# io-board-c-7.net
KiCad netlist of a schematic drawn in EAGLE
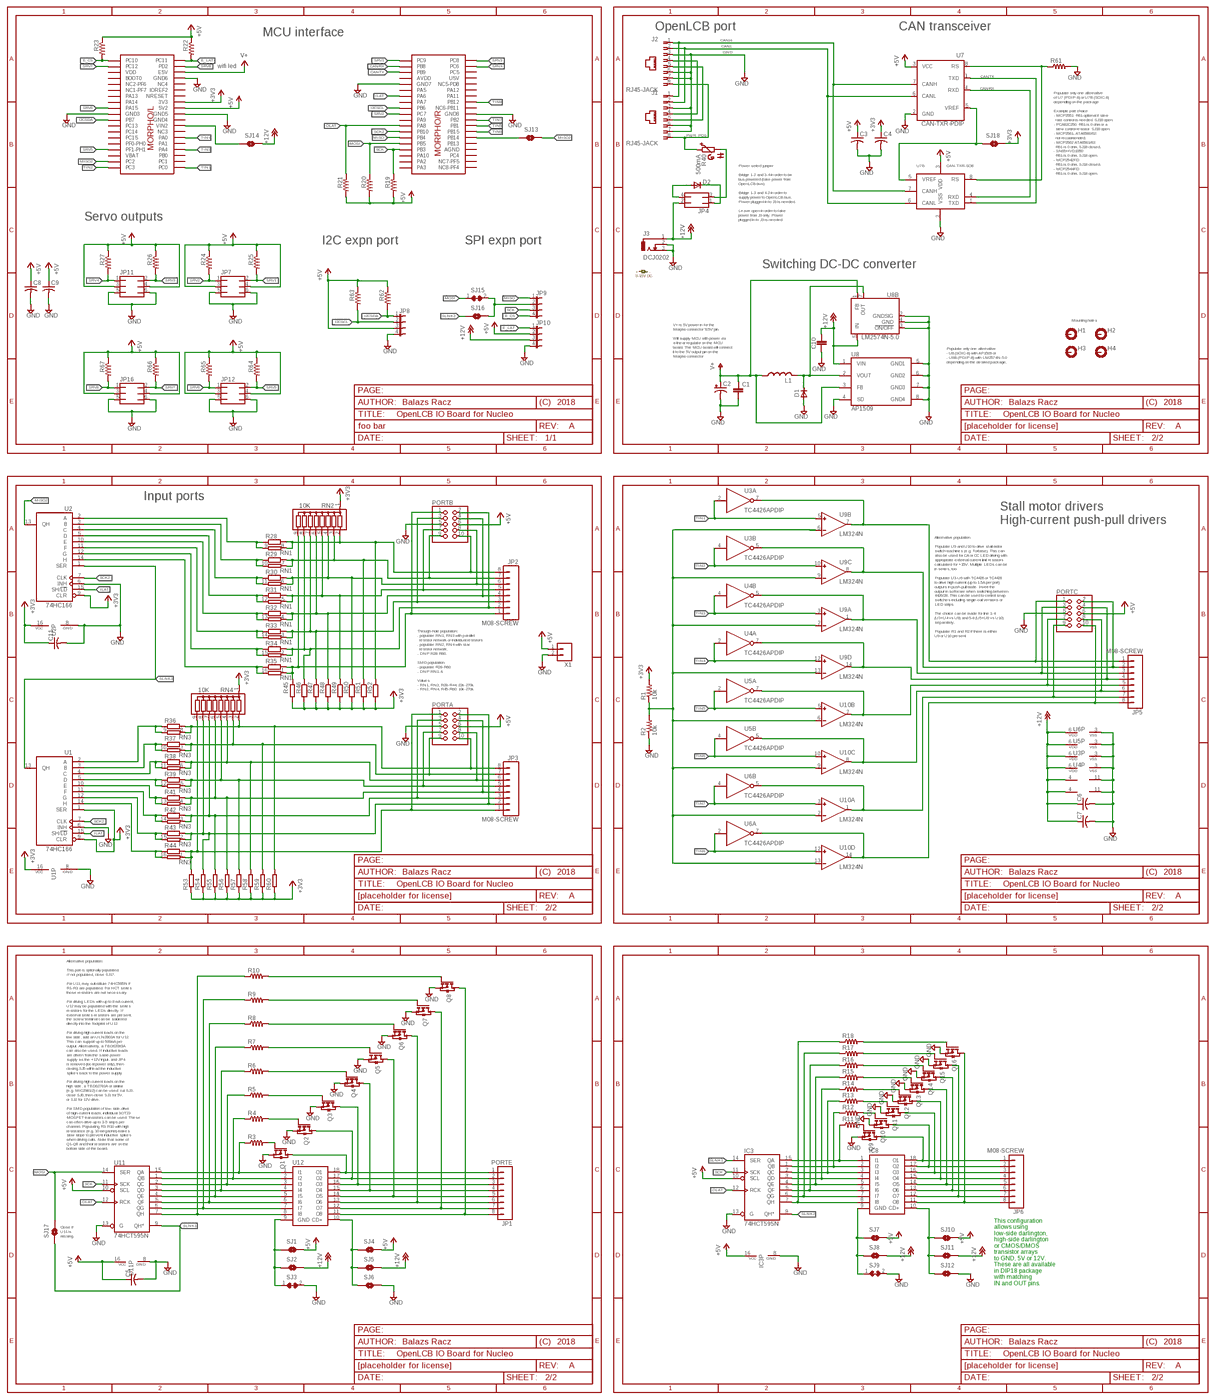
[diagram p0: schematic, sheet 1, overview]
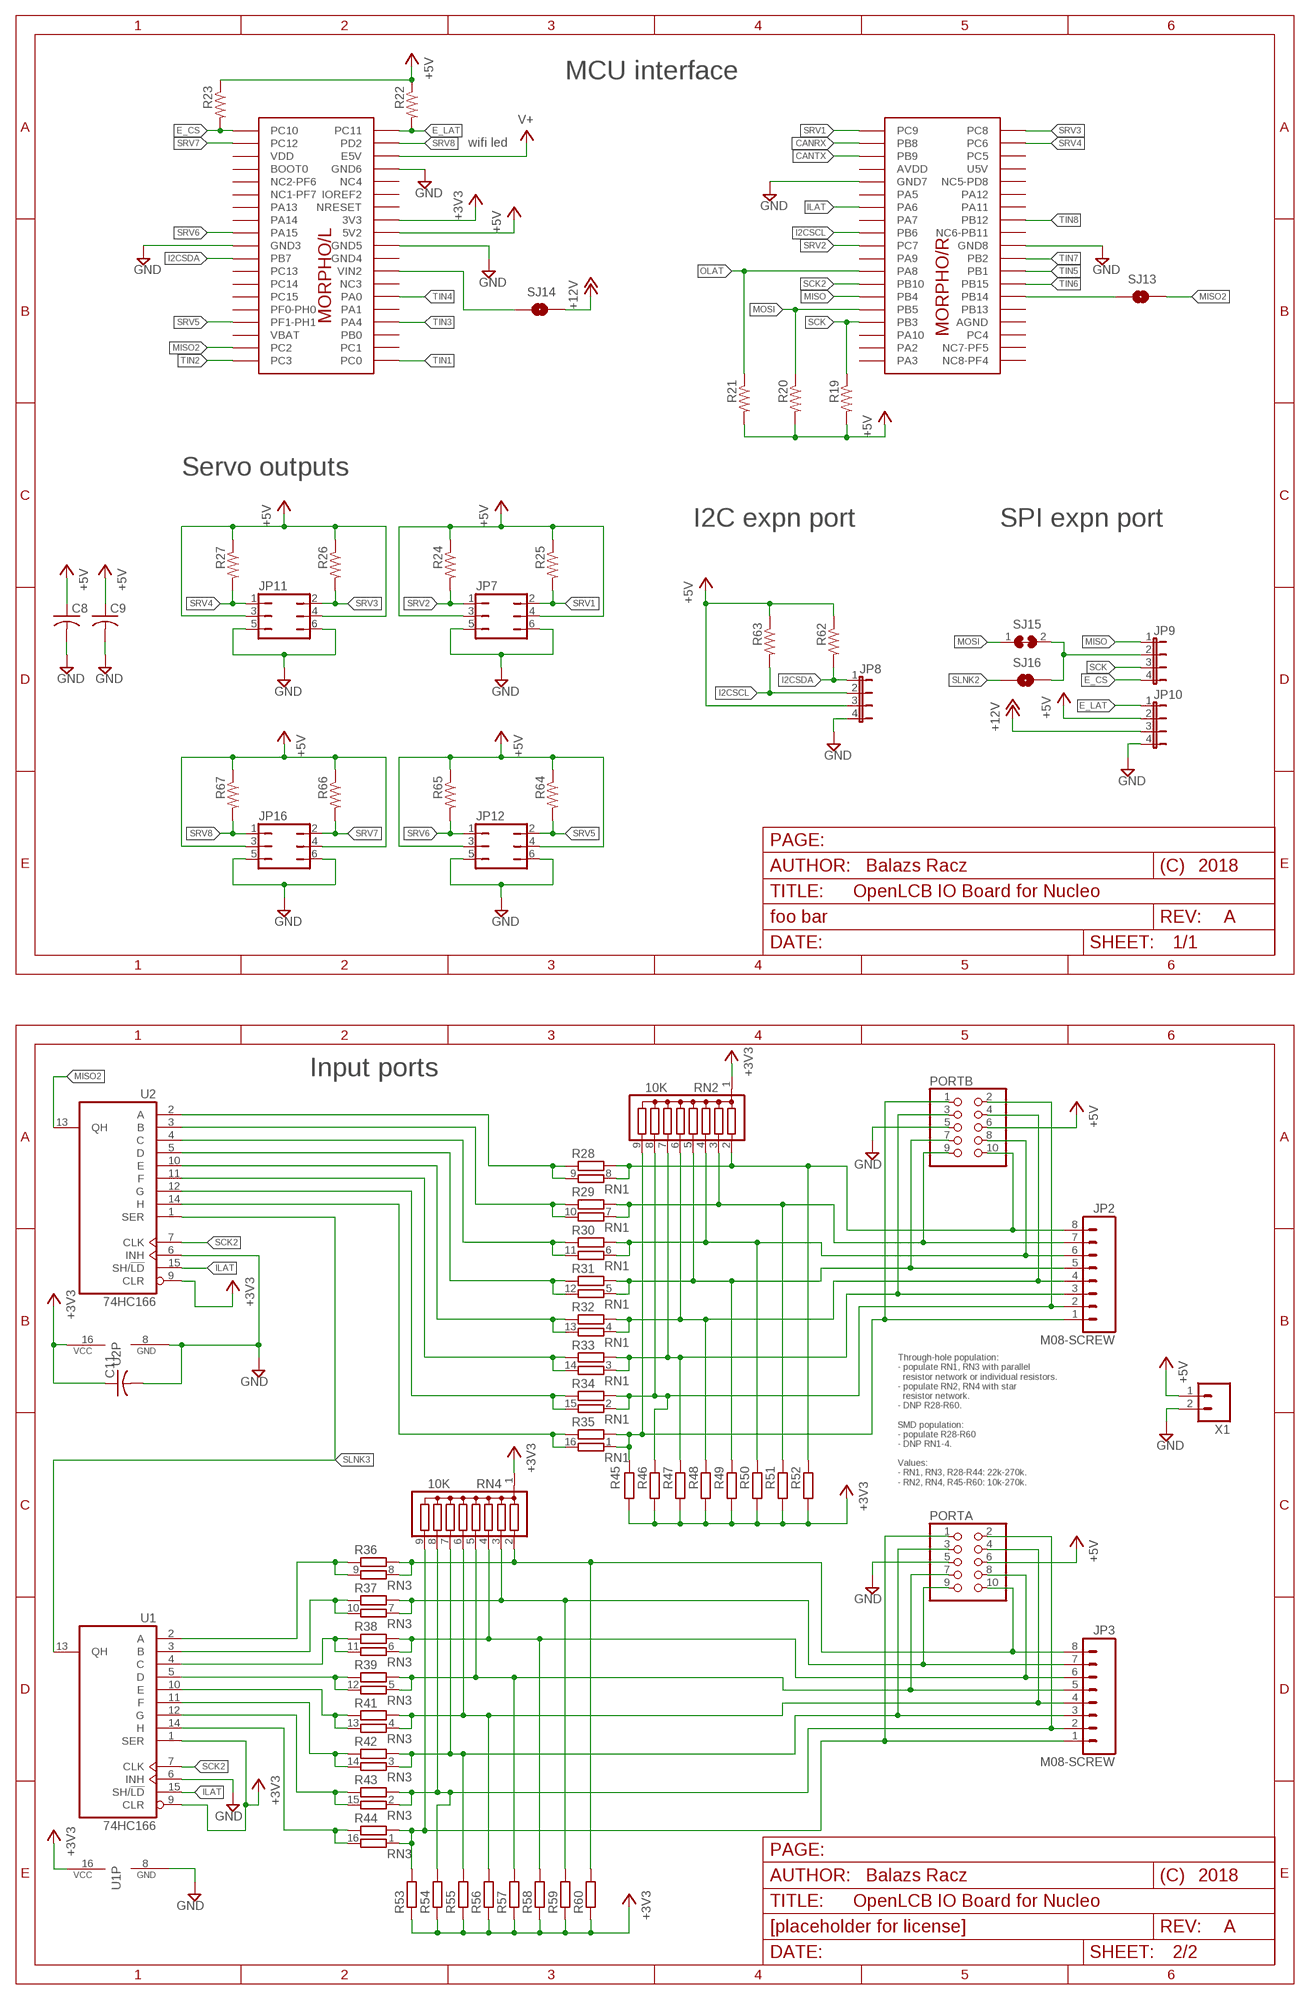
[diagram p1: schematic, sheet 1, part 1 of 4]
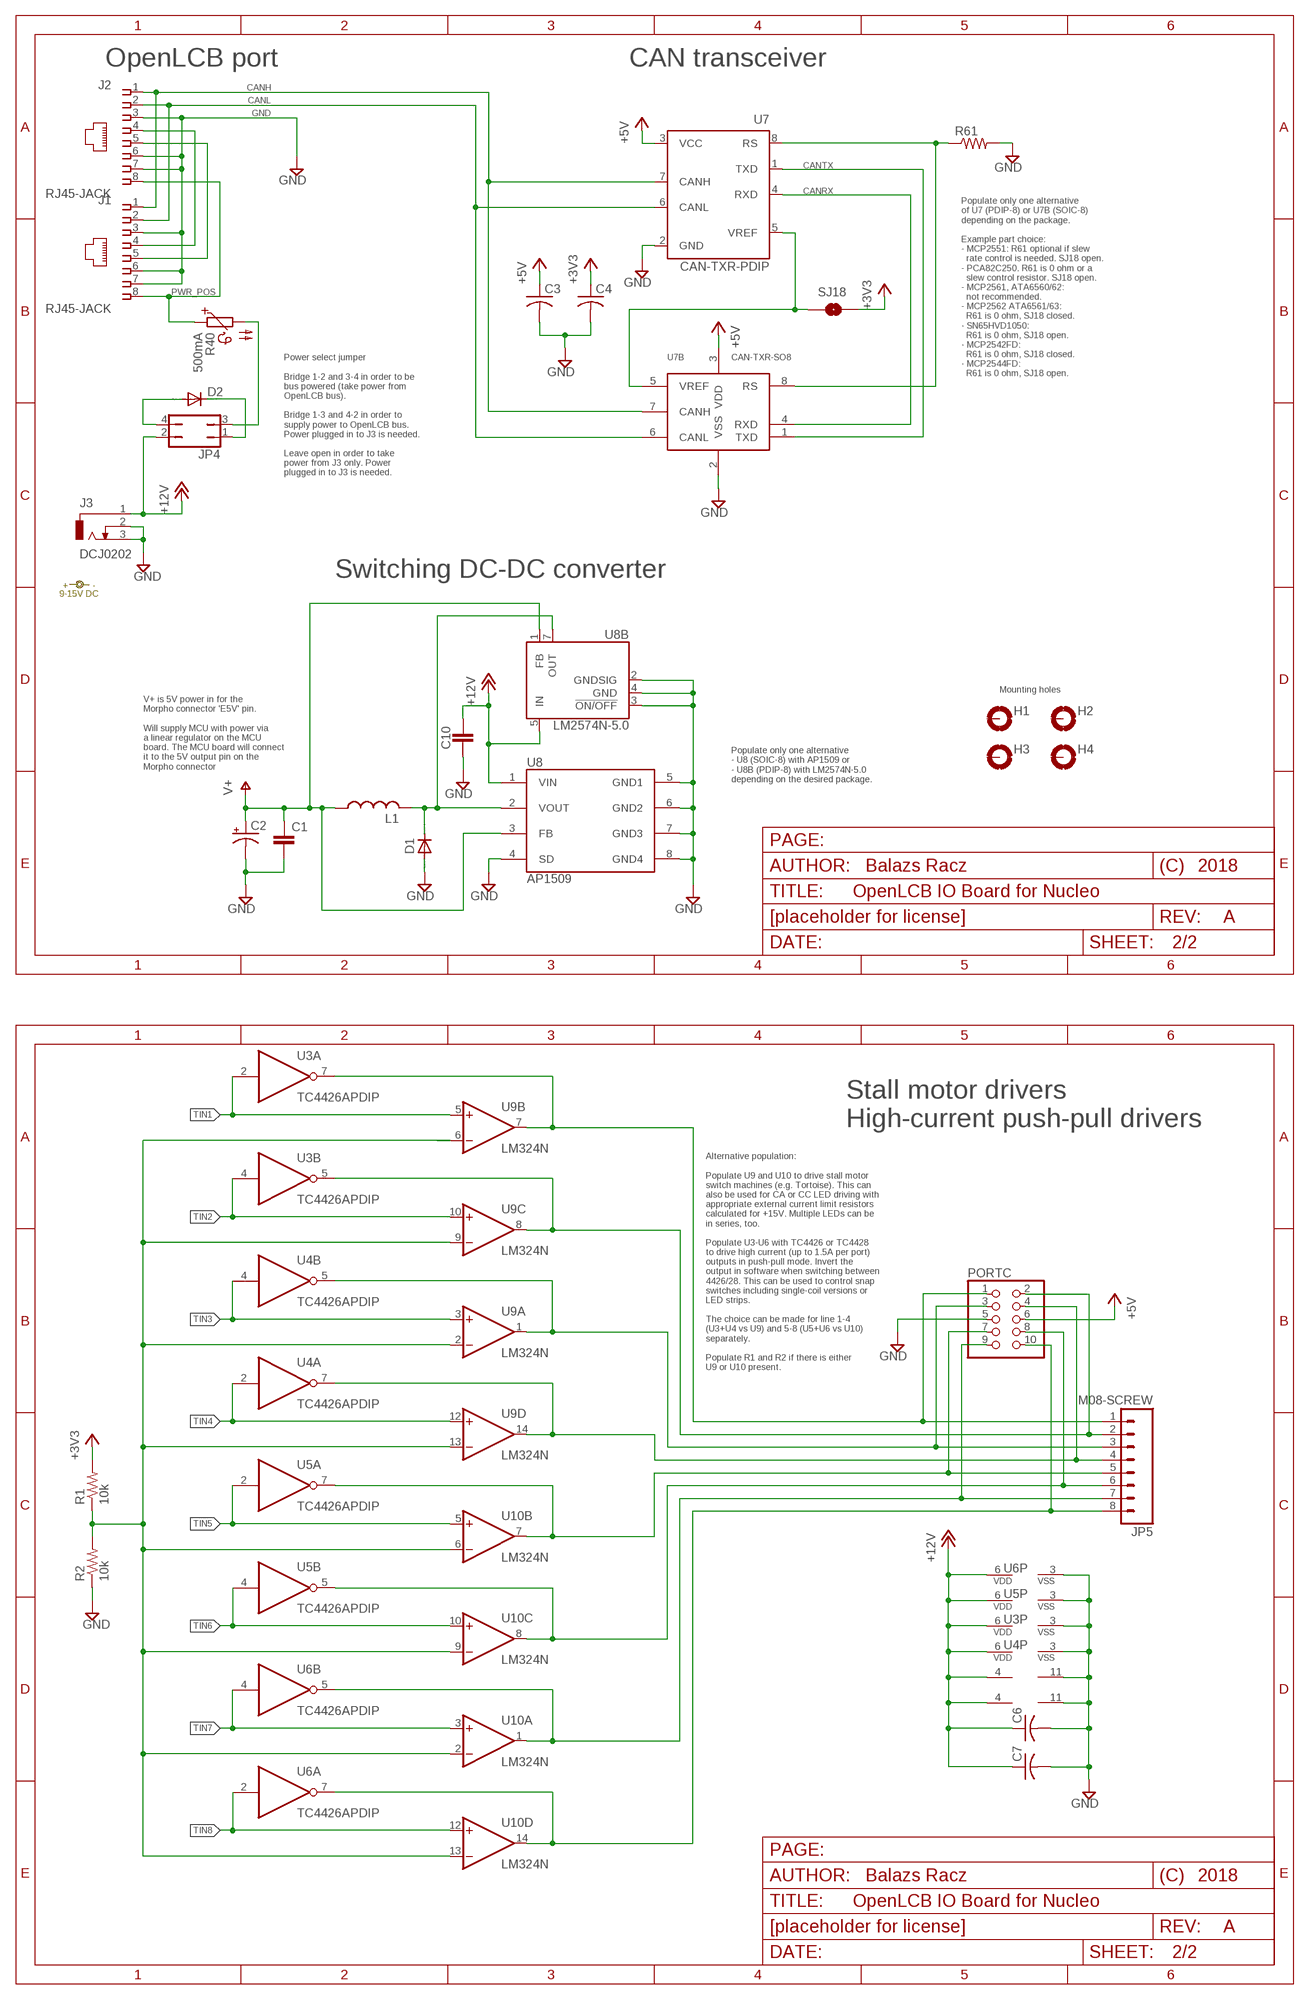
[diagram p2: schematic, sheet 1, part 2 of 4]
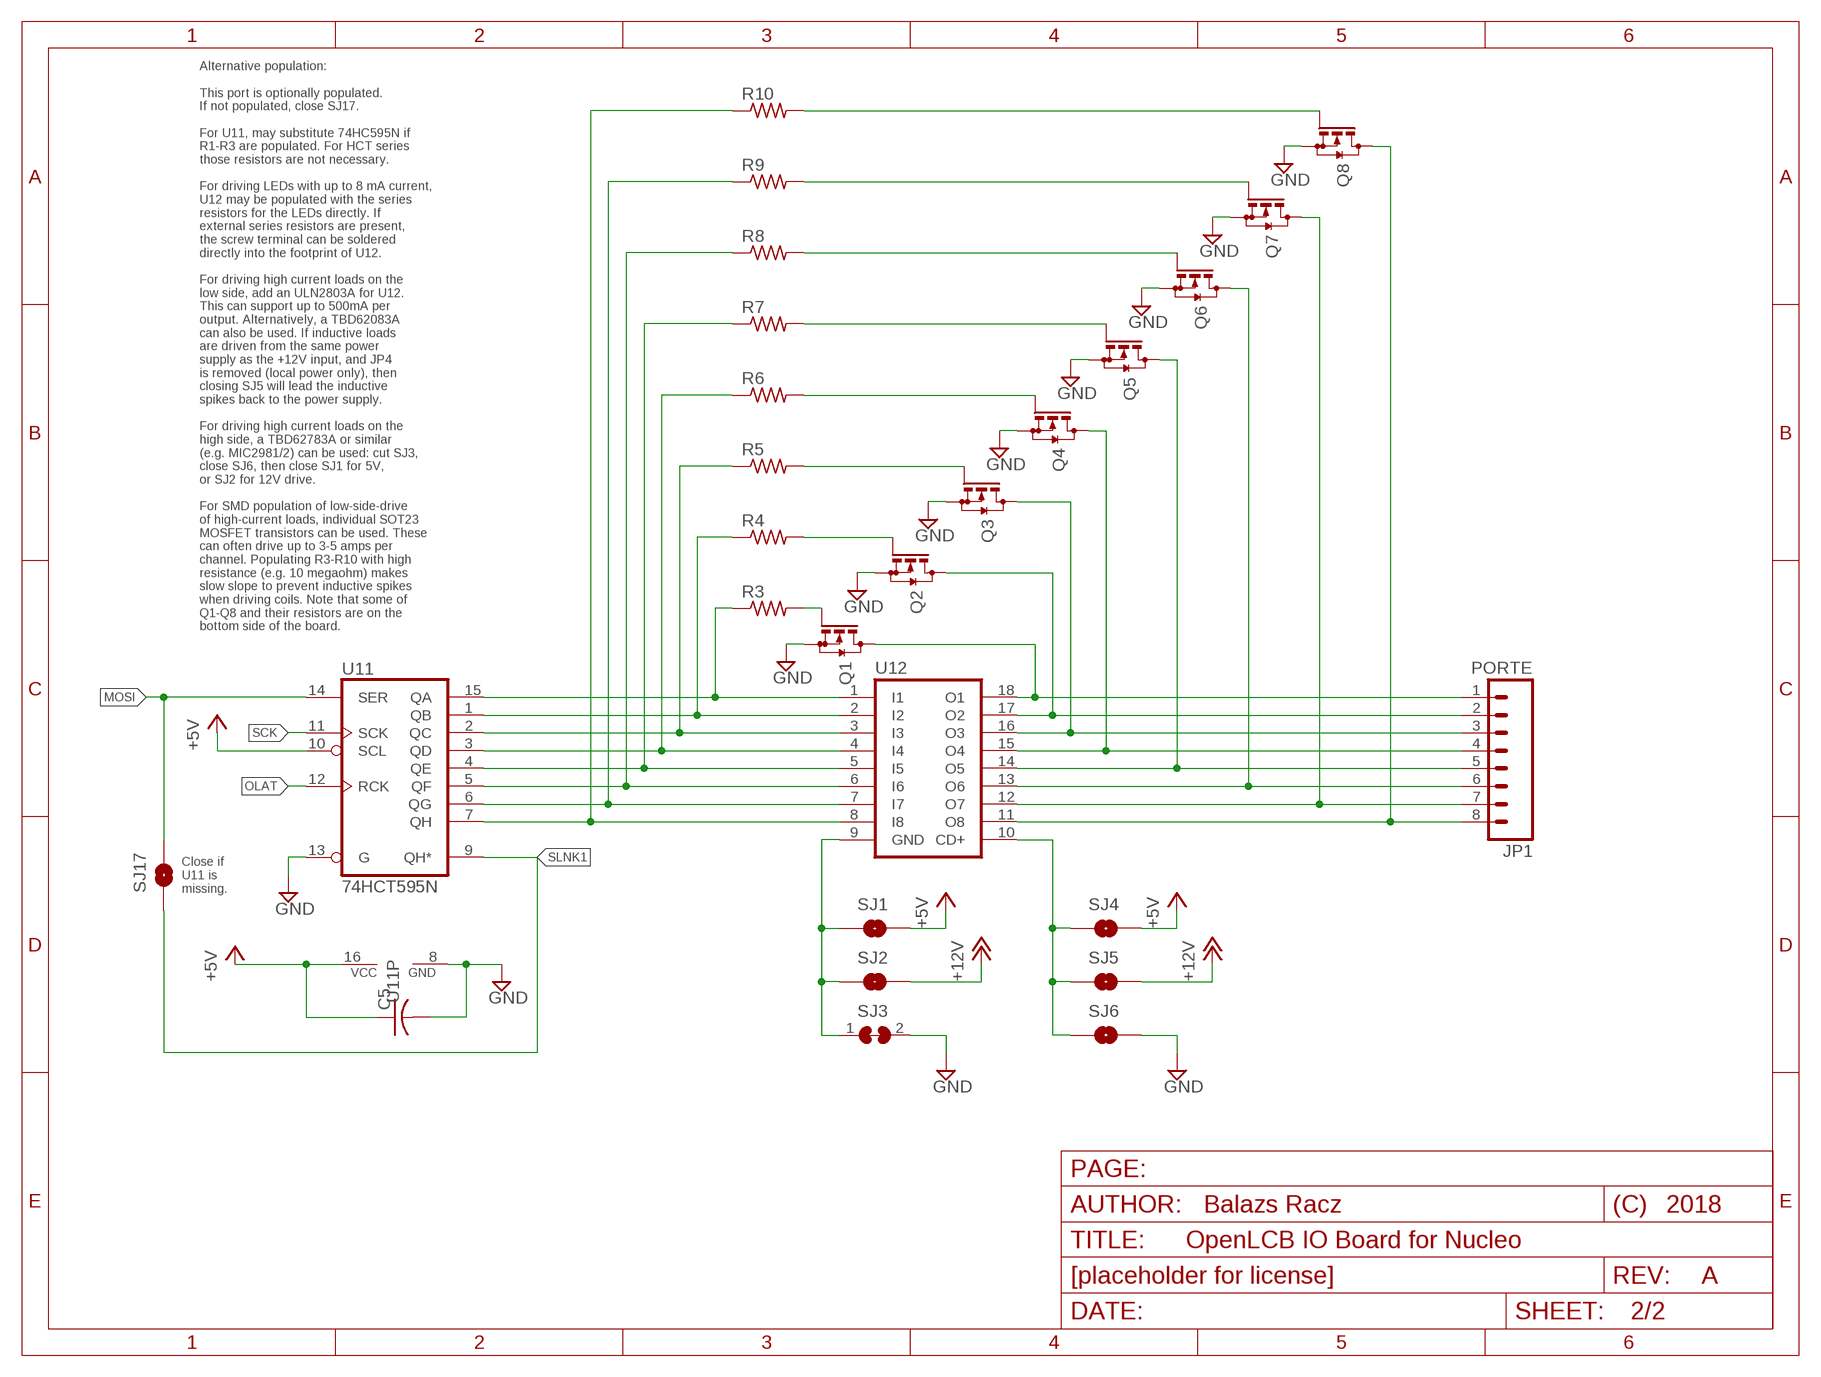
[diagram p3: schematic, sheet 1, part 3 of 4]
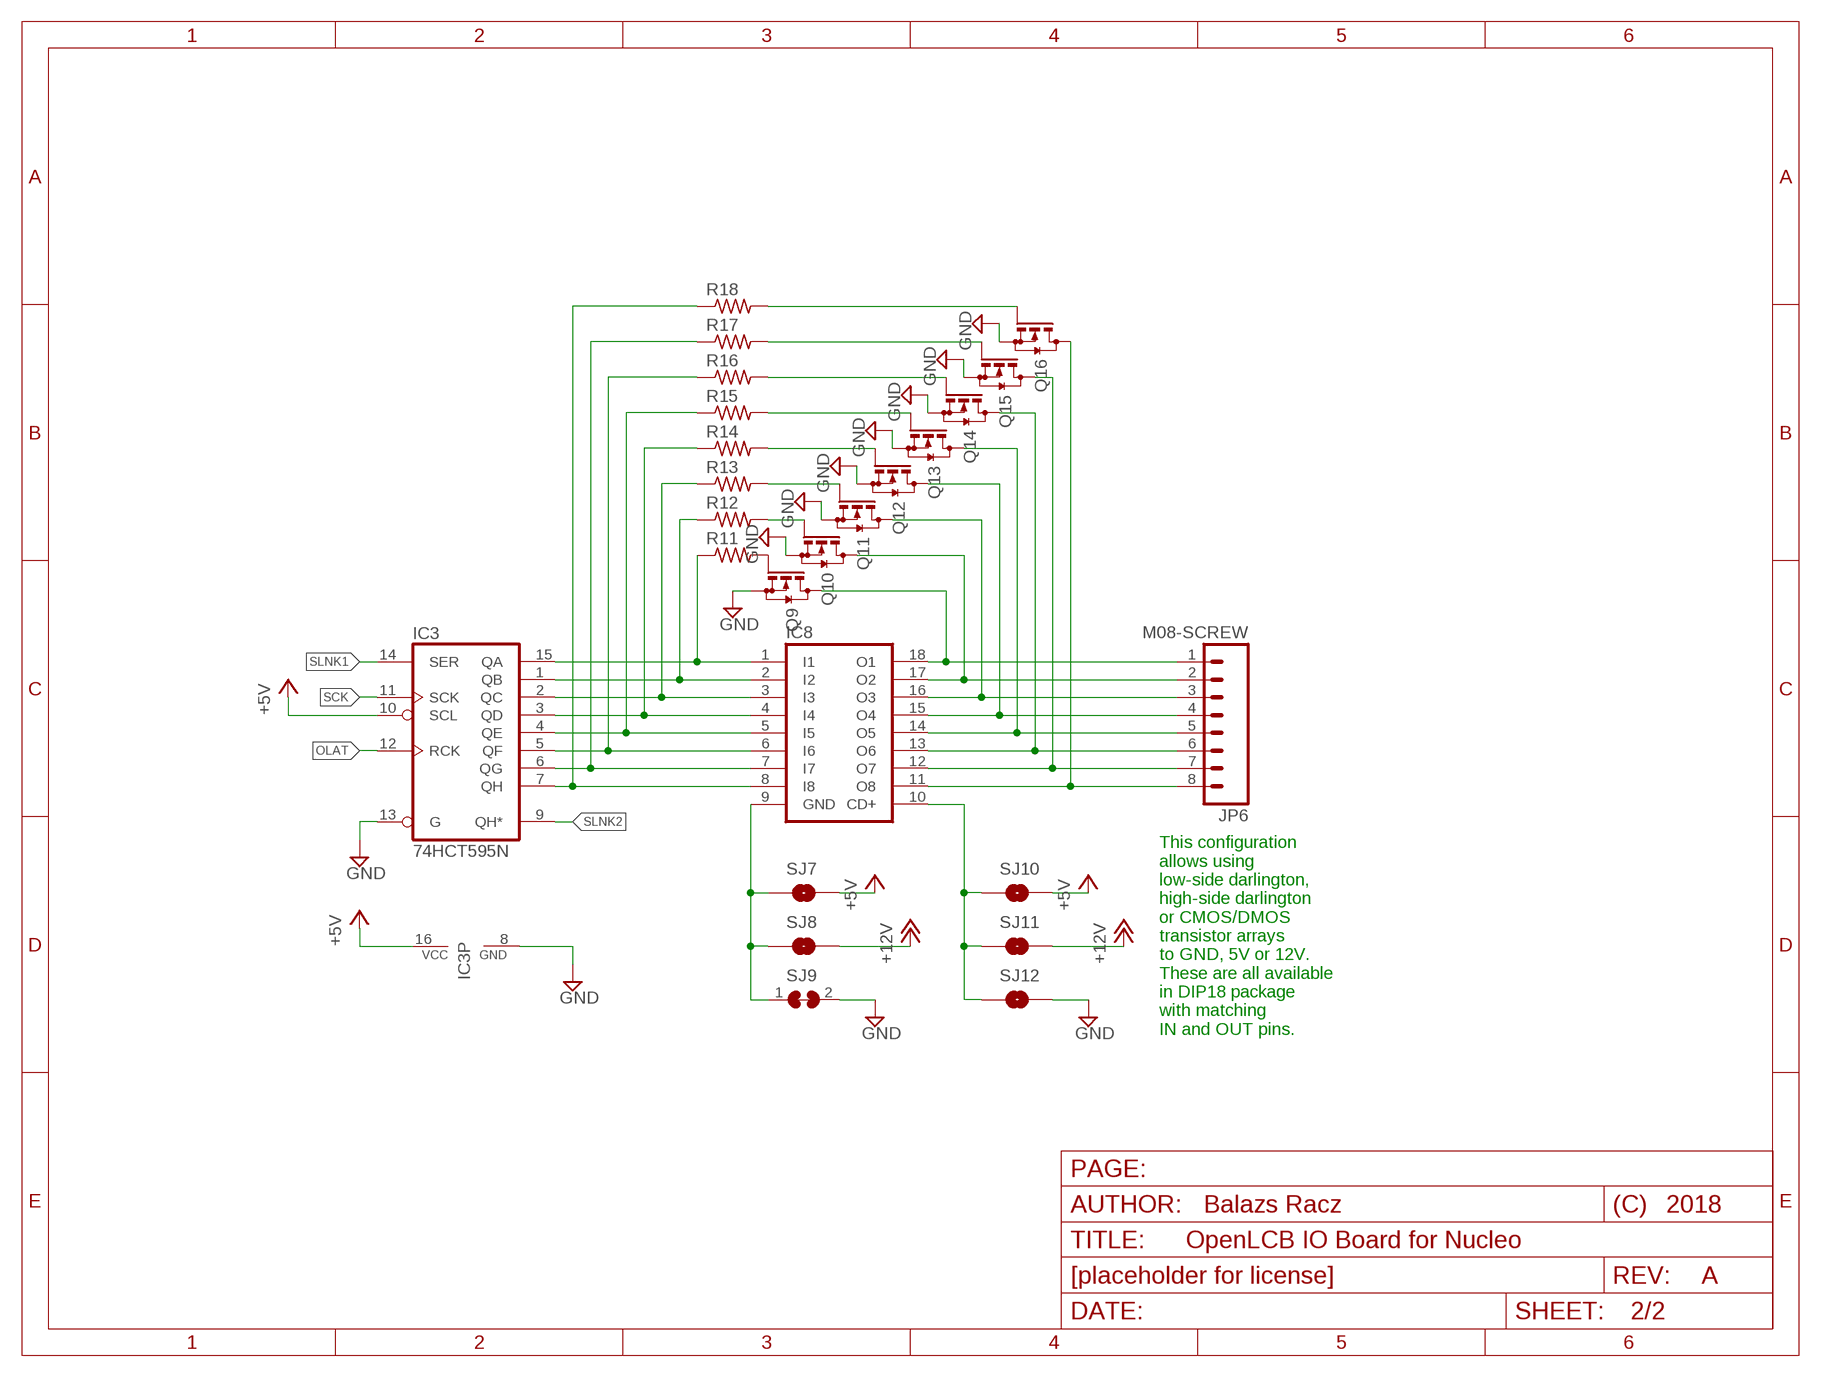
[diagram p4: schematic, sheet 1, part 4 of 4]

(export (version "E")
  (design (tool "Eeschema 10.0.6"))
  (components
    (comp (ref "+12V")
      (value "9-15V DC")
      (footprint "eagle-import:POWER_USAGE")
      (libsource (lib "eagle-import") (part "DOC-POWER_LABEL"))
    )
    (comp (ref "C1")
      (value "C-EUC1206")
      (footprint "eagle-import:C1206")
      (libsource (lib "eagle-import") (part "C-EUC1206"))
    )
    (comp (ref "C2")
      (value "CPOL-USE2.5-5")
      (footprint "eagle-import:E2,5-5")
      (libsource (lib "eagle-import") (part "CPOL-USE2.5-5"))
    )
    (comp (ref "C3")
      (value "C-USC0805")
      (footprint "eagle-import:C0805")
      (libsource (lib "eagle-import") (part "C-USC0805"))
    )
    (comp (ref "C4")
      (value "C-USC0805")
      (footprint "eagle-import:C0805")
      (libsource (lib "eagle-import") (part "C-USC0805"))
    )
    (comp (ref "C5")
      (value "C-USC0805")
      (footprint "eagle-import:C0805")
      (libsource (lib "eagle-import") (part "C-USC0805"))
    )
    (comp (ref "C6")
      (value "C-USC1206")
      (footprint "eagle-import:C1206")
      (libsource (lib "eagle-import") (part "C-USC1206"))
    )
    (comp (ref "C7")
      (value "C-USC1206")
      (footprint "eagle-import:C1206")
      (libsource (lib "eagle-import") (part "C-USC1206"))
    )
    (comp (ref "C8")
      (value "C-USC1206")
      (footprint "eagle-import:C1206")
      (libsource (lib "eagle-import") (part "C-USC1206"))
    )
    (comp (ref "C9")
      (value "C-USC1206")
      (footprint "eagle-import:C1206")
      (libsource (lib "eagle-import") (part "C-USC1206"))
    )
    (comp (ref "C10")
      (value "C-EUC1206")
      (footprint "eagle-import:C1206")
      (libsource (lib "eagle-import") (part "C-EUC1206"))
    )
    (comp (ref "C11")
      (value "C-USC0805")
      (footprint "eagle-import:C0805")
      (libsource (lib "eagle-import") (part "C-USC0805"))
    )
    (comp (ref "D1")
      (value "DIODE-DO41-7.6")
      (footprint "eagle-import:DO41-7.6")
      (libsource (lib "eagle-import") (part "DIODE-DO41-7.6"))
    )
    (comp (ref "D2")
      (value "DIODE-DO41-7.6")
      (footprint "eagle-import:DO41-7.6")
      (libsource (lib "eagle-import") (part "DIODE-DO41-7.6"))
    )
    (comp (ref "H1")
      (value "MOUNT-PAD-ROUND3.3")
      (footprint "eagle-import:3,3-PAD")
      (libsource (lib "eagle-import") (part "MOUNT-PAD-ROUND3.3"))
    )
    (comp (ref "H2")
      (value "MOUNT-PAD-ROUND3.3")
      (footprint "eagle-import:3,3-PAD")
      (libsource (lib "eagle-import") (part "MOUNT-PAD-ROUND3.3"))
    )
    (comp (ref "H3")
      (value "MOUNT-PAD-ROUND3.3")
      (footprint "eagle-import:3,3-PAD")
      (libsource (lib "eagle-import") (part "MOUNT-PAD-ROUND3.3"))
    )
    (comp (ref "H4")
      (value "MOUNT-PAD-ROUND3.3")
      (footprint "eagle-import:3,3-PAD")
      (libsource (lib "eagle-import") (part "MOUNT-PAD-ROUND3.3"))
    )
    (comp (ref "IC3")
      (value "74HCT595N")
      (footprint "eagle-import:DIL16")
      (libsource (lib "eagle-import") (part "74595NHCT"))
    )
    (comp (ref "IC8")
      (value "ULN2803A")
      (footprint "eagle-import:DIL18-THIN")
      (libsource (lib "eagle-import") (part "ULN2803A"))
    )
    (comp (ref "J1")
      (value "RJ45-JACK")
      (footprint "eagle-import:RJ45-PULSE-E5J88")
      (libsource (lib "eagle-import") (part "RJ45-JACKRJ45-PULSE-E5J00"))
    )
    (comp (ref "J2")
      (value "RJ45-JACK")
      (footprint "eagle-import:RJ45-PULSE-E5J88")
      (libsource (lib "eagle-import") (part "RJ45-JACKRJ45-PULSE-E5J00"))
    )
    (comp (ref "J3")
      (value "DCJ0202")
      (footprint "eagle-import:DCJ0202")
      (libsource (lib "eagle-import") (part "DCJ0202"))
    )
    (comp (ref "JP1")
      (value "PORTE")
      (footprint "eagle-import:1X08_TERMINAL")
      (libsource (lib "eagle-import") (part "M08-SCREW"))
    )
    (comp (ref "JP2")
      (value "M08-SCREW")
      (footprint "eagle-import:1X08_TERMINAL")
      (libsource (lib "eagle-import") (part "M08-SCREW"))
    )
    (comp (ref "JP3")
      (value "M08-SCREW")
      (footprint "eagle-import:1X08_TERMINAL")
      (libsource (lib "eagle-import") (part "M08-SCREW"))
    )
    (comp (ref "JP4")
      (value "JP2Q")
      (footprint "eagle-import:JP2Q")
      (libsource (lib "eagle-import") (part "JP2Q"))
    )
    (comp (ref "JP5")
      (value "M08-SCREW")
      (footprint "eagle-import:1X08_TERMINAL")
      (libsource (lib "eagle-import") (part "M08-SCREW"))
    )
    (comp (ref "JP6")
      (value "M08-SCREW")
      (footprint "eagle-import:1X08_TERMINAL")
      (libsource (lib "eagle-import") (part "M08-SCREW"))
    )
    (comp (ref "JP7")
      (value "JP3Q")
      (footprint "eagle-import:JP3Q")
      (libsource (lib "eagle-import") (part "JP3Q"))
    )
    (comp (ref "JP8")
      (value "JP4-FLAT")
      (footprint "eagle-import:JP4F")
      (libsource (lib "eagle-import") (part "JP4-FLAT"))
    )
    (comp (ref "JP9")
      (value "JP4-FLAT")
      (footprint "eagle-import:JP4F")
      (libsource (lib "eagle-import") (part "JP4-FLAT"))
    )
    (comp (ref "JP10")
      (value "JP4-FLAT")
      (footprint "eagle-import:JP4F")
      (libsource (lib "eagle-import") (part "JP4-FLAT"))
    )
    (comp (ref "JP11")
      (value "JP3Q")
      (footprint "eagle-import:JP3Q")
      (libsource (lib "eagle-import") (part "JP3Q"))
    )
    (comp (ref "JP12")
      (value "JP3Q")
      (footprint "eagle-import:JP3Q")
      (libsource (lib "eagle-import") (part "JP3Q"))
    )
    (comp (ref "JP16")
      (value "JP3Q")
      (footprint "eagle-import:JP3Q")
      (libsource (lib "eagle-import") (part "JP3Q"))
    )
    (comp (ref "L1")
      (value "L-US")
      (footprint "eagle-import:L5-8,5")
      (libsource (lib "eagle-import") (part "L-US"))
    )
    (comp (ref "PORTA")
      (value "PINHD-2X5CN")
      (footprint "eagle-import:CON10M")
      (libsource (lib "eagle-import") (part "PINHD-2X5CN"))
    )
    (comp (ref "PORTB")
      (value "PINHD-2X5CN")
      (footprint "eagle-import:CON10M")
      (libsource (lib "eagle-import") (part "PINHD-2X5CN"))
    )
    (comp (ref "PORTC")
      (value "PINHD-2X5CN")
      (footprint "eagle-import:CON10M")
      (libsource (lib "eagle-import") (part "PINHD-2X5CN"))
    )
    (comp (ref "Q1")
      (value "BSS123")
      (footprint "eagle-import:SOT23")
      (libsource (lib "eagle-import") (part "BSS123"))
    )
    (comp (ref "Q2")
      (value "BSS123")
      (footprint "eagle-import:SOT23")
      (libsource (lib "eagle-import") (part "BSS123"))
    )
    (comp (ref "Q3")
      (value "BSS123")
      (footprint "eagle-import:SOT23")
      (libsource (lib "eagle-import") (part "BSS123"))
    )
    (comp (ref "Q4")
      (value "BSS123")
      (footprint "eagle-import:SOT23")
      (libsource (lib "eagle-import") (part "BSS123"))
    )
    (comp (ref "Q5")
      (value "BSS123")
      (footprint "eagle-import:SOT23")
      (libsource (lib "eagle-import") (part "BSS123"))
    )
    (comp (ref "Q6")
      (value "BSS123")
      (footprint "eagle-import:SOT23")
      (libsource (lib "eagle-import") (part "BSS123"))
    )
    (comp (ref "Q7")
      (value "BSS123")
      (footprint "eagle-import:SOT23")
      (libsource (lib "eagle-import") (part "BSS123"))
    )
    (comp (ref "Q8")
      (value "BSS123")
      (footprint "eagle-import:SOT23")
      (libsource (lib "eagle-import") (part "BSS123"))
    )
    (comp (ref "Q9")
      (value "BSS123")
      (footprint "eagle-import:SOT23")
      (libsource (lib "eagle-import") (part "BSS123"))
    )
    (comp (ref "Q10")
      (value "BSS123")
      (footprint "eagle-import:SOT23")
      (libsource (lib "eagle-import") (part "BSS123"))
    )
    (comp (ref "Q11")
      (value "BSS123")
      (footprint "eagle-import:SOT23")
      (libsource (lib "eagle-import") (part "BSS123"))
    )
    (comp (ref "Q12")
      (value "BSS123")
      (footprint "eagle-import:SOT23")
      (libsource (lib "eagle-import") (part "BSS123"))
    )
    (comp (ref "Q13")
      (value "BSS123")
      (footprint "eagle-import:SOT23")
      (libsource (lib "eagle-import") (part "BSS123"))
    )
    (comp (ref "Q14")
      (value "BSS123")
      (footprint "eagle-import:SOT23")
      (libsource (lib "eagle-import") (part "BSS123"))
    )
    (comp (ref "Q15")
      (value "BSS123")
      (footprint "eagle-import:SOT23")
      (libsource (lib "eagle-import") (part "BSS123"))
    )
    (comp (ref "Q16")
      (value "BSS123")
      (footprint "eagle-import:SOT23")
      (libsource (lib "eagle-import") (part "BSS123"))
    )
    (comp (ref "R1")
      (value "10k")
      (footprint "eagle-import:R0805")
      (libsource (lib "eagle-import") (part "R-US_R0805"))
    )
    (comp (ref "R2")
      (value "10k")
      (footprint "eagle-import:R0805")
      (libsource (lib "eagle-import") (part "R-US_R0805"))
    )
    (comp (ref "R3")
      (value "R-US_R0603")
      (footprint "eagle-import:R0603")
      (libsource (lib "eagle-import") (part "R-US_R0603"))
    )
    (comp (ref "R4")
      (value "R-US_R0603")
      (footprint "eagle-import:R0603")
      (libsource (lib "eagle-import") (part "R-US_R0603"))
    )
    (comp (ref "R5")
      (value "R-US_R0603")
      (footprint "eagle-import:R0603")
      (libsource (lib "eagle-import") (part "R-US_R0603"))
    )
    (comp (ref "R6")
      (value "R-US_R0603")
      (footprint "eagle-import:R0603")
      (libsource (lib "eagle-import") (part "R-US_R0603"))
    )
    (comp (ref "R7")
      (value "R-US_R0603")
      (footprint "eagle-import:R0603")
      (libsource (lib "eagle-import") (part "R-US_R0603"))
    )
    (comp (ref "R8")
      (value "R-US_R0603")
      (footprint "eagle-import:R0603")
      (libsource (lib "eagle-import") (part "R-US_R0603"))
    )
    (comp (ref "R9")
      (value "R-US_R0603")
      (footprint "eagle-import:R0603")
      (libsource (lib "eagle-import") (part "R-US_R0603"))
    )
    (comp (ref "R10")
      (value "R-US_R0603")
      (footprint "eagle-import:R0603")
      (libsource (lib "eagle-import") (part "R-US_R0603"))
    )
    (comp (ref "R11")
      (value "R-US_R0603")
      (footprint "eagle-import:R0603")
      (libsource (lib "eagle-import") (part "R-US_R0603"))
    )
    (comp (ref "R12")
      (value "R-US_R0603")
      (footprint "eagle-import:R0603")
      (libsource (lib "eagle-import") (part "R-US_R0603"))
    )
    (comp (ref "R13")
      (value "R-US_R0603")
      (footprint "eagle-import:R0603")
      (libsource (lib "eagle-import") (part "R-US_R0603"))
    )
    (comp (ref "R14")
      (value "R-US_R0603")
      (footprint "eagle-import:R0603")
      (libsource (lib "eagle-import") (part "R-US_R0603"))
    )
    (comp (ref "R15")
      (value "R-US_R0603")
      (footprint "eagle-import:R0603")
      (libsource (lib "eagle-import") (part "R-US_R0603"))
    )
    (comp (ref "R16")
      (value "R-US_R0603")
      (footprint "eagle-import:R0603")
      (libsource (lib "eagle-import") (part "R-US_R0603"))
    )
    (comp (ref "R17")
      (value "R-US_R0603")
      (footprint "eagle-import:R0603")
      (libsource (lib "eagle-import") (part "R-US_R0603"))
    )
    (comp (ref "R18")
      (value "R-US_R0603")
      (footprint "eagle-import:R0603")
      (libsource (lib "eagle-import") (part "R-US_R0603"))
    )
    (comp (ref "R19")
      (value "R-US_R0805")
      (footprint "eagle-import:R0805")
      (libsource (lib "eagle-import") (part "rcl_334_R-US_R0805"))
    )
    (comp (ref "R20")
      (value "R-US_R0805")
      (footprint "eagle-import:R0805")
      (libsource (lib "eagle-import") (part "rcl_334_R-US_R0805"))
    )
    (comp (ref "R21")
      (value "R-US_R0805")
      (footprint "eagle-import:R0805")
      (libsource (lib "eagle-import") (part "rcl_334_R-US_R0805"))
    )
    (comp (ref "R22")
      (value "R-US_R0805")
      (footprint "eagle-import:R0805")
      (libsource (lib "eagle-import") (part "rcl_334_R-US_R0805"))
    )
    (comp (ref "R23")
      (value "R-US_R0805")
      (footprint "eagle-import:R0805")
      (libsource (lib "eagle-import") (part "rcl_334_R-US_R0805"))
    )
    (comp (ref "R24")
      (value "R-US_R0805")
      (footprint "eagle-import:R0805")
      (libsource (lib "eagle-import") (part "rcl_334_R-US_R0805"))
    )
    (comp (ref "R25")
      (value "R-US_R0805")
      (footprint "eagle-import:R0805")
      (libsource (lib "eagle-import") (part "rcl_334_R-US_R0805"))
    )
    (comp (ref "R26")
      (value "R-US_R0805")
      (footprint "eagle-import:R0805")
      (libsource (lib "eagle-import") (part "rcl_334_R-US_R0805"))
    )
    (comp (ref "R27")
      (value "R-US_R0805")
      (footprint "eagle-import:R0805")
      (libsource (lib "eagle-import") (part "rcl_334_R-US_R0805"))
    )
    (comp (ref "R28")
      (value "R-EU_R0603")
      (footprint "eagle-import:R0603")
      (libsource (lib "eagle-import") (part "R-EU_R0603"))
    )
    (comp (ref "R29")
      (value "R-EU_R0603")
      (footprint "eagle-import:R0603")
      (libsource (lib "eagle-import") (part "R-EU_R0603"))
    )
    (comp (ref "R30")
      (value "R-EU_R0603")
      (footprint "eagle-import:R0603")
      (libsource (lib "eagle-import") (part "R-EU_R0603"))
    )
    (comp (ref "R31")
      (value "R-EU_R0603")
      (footprint "eagle-import:R0603")
      (libsource (lib "eagle-import") (part "R-EU_R0603"))
    )
    (comp (ref "R32")
      (value "R-EU_R0603")
      (footprint "eagle-import:R0603")
      (libsource (lib "eagle-import") (part "R-EU_R0603"))
    )
    (comp (ref "R33")
      (value "R-EU_R0603")
      (footprint "eagle-import:R0603")
      (libsource (lib "eagle-import") (part "R-EU_R0603"))
    )
    (comp (ref "R34")
      (value "R-EU_R0603")
      (footprint "eagle-import:R0603")
      (libsource (lib "eagle-import") (part "R-EU_R0603"))
    )
    (comp (ref "R35")
      (value "R-EU_R0603")
      (footprint "eagle-import:R0603")
      (libsource (lib "eagle-import") (part "R-EU_R0603"))
    )
    (comp (ref "R36")
      (value "R-EU_R0603")
      (footprint "eagle-import:R0603")
      (libsource (lib "eagle-import") (part "R-EU_R0603"))
    )
    (comp (ref "R37")
      (value "R-EU_R0603")
      (footprint "eagle-import:R0603")
      (libsource (lib "eagle-import") (part "R-EU_R0603"))
    )
    (comp (ref "R38")
      (value "R-EU_R0603")
      (footprint "eagle-import:R0603")
      (libsource (lib "eagle-import") (part "R-EU_R0603"))
    )
    (comp (ref "R39")
      (value "R-EU_R0603")
      (footprint "eagle-import:R0603")
      (libsource (lib "eagle-import") (part "R-EU_R0603"))
    )
    (comp (ref "R40")
      (value "500mA")
      (footprint "eagle-import:PTC1812")
      (libsource (lib "eagle-import") (part "PTC_1812"))
    )
    (comp (ref "R41")
      (value "R-EU_R0603")
      (footprint "eagle-import:R0603")
      (libsource (lib "eagle-import") (part "R-EU_R0603"))
    )
    (comp (ref "R42")
      (value "R-EU_R0603")
      (footprint "eagle-import:R0603")
      (libsource (lib "eagle-import") (part "R-EU_R0603"))
    )
    (comp (ref "R43")
      (value "R-EU_R0603")
      (footprint "eagle-import:R0603")
      (libsource (lib "eagle-import") (part "R-EU_R0603"))
    )
    (comp (ref "R44")
      (value "R-EU_R0603")
      (footprint "eagle-import:R0603")
      (libsource (lib "eagle-import") (part "R-EU_R0603"))
    )
    (comp (ref "R45")
      (value "R-EU_R0603")
      (footprint "eagle-import:R0603")
      (libsource (lib "eagle-import") (part "R-EU_R0603"))
    )
    (comp (ref "R46")
      (value "R-EU_R0603")
      (footprint "eagle-import:R0603")
      (libsource (lib "eagle-import") (part "R-EU_R0603"))
    )
    (comp (ref "R47")
      (value "R-EU_R0603")
      (footprint "eagle-import:R0603")
      (libsource (lib "eagle-import") (part "R-EU_R0603"))
    )
    (comp (ref "R48")
      (value "R-EU_R0603")
      (footprint "eagle-import:R0603")
      (libsource (lib "eagle-import") (part "R-EU_R0603"))
    )
    (comp (ref "R49")
      (value "R-EU_R0603")
      (footprint "eagle-import:R0603")
      (libsource (lib "eagle-import") (part "R-EU_R0603"))
    )
    (comp (ref "R50")
      (value "R-EU_R0603")
      (footprint "eagle-import:R0603")
      (libsource (lib "eagle-import") (part "R-EU_R0603"))
    )
    (comp (ref "R51")
      (value "R-EU_R0603")
      (footprint "eagle-import:R0603")
      (libsource (lib "eagle-import") (part "R-EU_R0603"))
    )
    (comp (ref "R52")
      (value "R-EU_R0603")
      (footprint "eagle-import:R0603")
      (libsource (lib "eagle-import") (part "R-EU_R0603"))
    )
    (comp (ref "R53")
      (value "R-EU_R0603")
      (footprint "eagle-import:R0603")
      (libsource (lib "eagle-import") (part "R-EU_R0603"))
    )
    (comp (ref "R54")
      (value "R-EU_R0603")
      (footprint "eagle-import:R0603")
      (libsource (lib "eagle-import") (part "R-EU_R0603"))
    )
    (comp (ref "R55")
      (value "R-EU_R0603")
      (footprint "eagle-import:R0603")
      (libsource (lib "eagle-import") (part "R-EU_R0603"))
    )
    (comp (ref "R56")
      (value "R-EU_R0603")
      (footprint "eagle-import:R0603")
      (libsource (lib "eagle-import") (part "R-EU_R0603"))
    )
    (comp (ref "R57")
      (value "R-EU_R0603")
      (footprint "eagle-import:R0603")
      (libsource (lib "eagle-import") (part "R-EU_R0603"))
    )
    (comp (ref "R58")
      (value "R-EU_R0603")
      (footprint "eagle-import:R0603")
      (libsource (lib "eagle-import") (part "R-EU_R0603"))
    )
    (comp (ref "R59")
      (value "R-EU_R0603")
      (footprint "eagle-import:R0603")
      (libsource (lib "eagle-import") (part "R-EU_R0603"))
    )
    (comp (ref "R60")
      (value "R-EU_R0603")
      (footprint "eagle-import:R0603")
      (libsource (lib "eagle-import") (part "R-EU_R0603"))
    )
    (comp (ref "R61")
      (value "R-US_R0805")
      (footprint "eagle-import:R0805")
      (libsource (lib "eagle-import") (part "rcl_334_R-US_R0805"))
    )
    (comp (ref "R62")
      (value "R-US_R0805")
      (footprint "eagle-import:R0805")
      (libsource (lib "eagle-import") (part "rcl_334_R-US_R0805"))
    )
    (comp (ref "R63")
      (value "R-US_R0805")
      (footprint "eagle-import:R0805")
      (libsource (lib "eagle-import") (part "rcl_334_R-US_R0805"))
    )
    (comp (ref "R64")
      (value "R-US_R0805")
      (footprint "eagle-import:R0805")
      (libsource (lib "eagle-import") (part "rcl_334_R-US_R0805"))
    )
    (comp (ref "R65")
      (value "R-US_R0805")
      (footprint "eagle-import:R0805")
      (libsource (lib "eagle-import") (part "rcl_334_R-US_R0805"))
    )
    (comp (ref "R66")
      (value "R-US_R0805")
      (footprint "eagle-import:R0805")
      (libsource (lib "eagle-import") (part "rcl_334_R-US_R0805"))
    )
    (comp (ref "R67")
      (value "R-US_R0805")
      (footprint "eagle-import:R0805")
      (libsource (lib "eagle-import") (part "rcl_334_R-US_R0805"))
    )
    (comp (ref "RN1")
      (value "8R-P")
      (footprint "eagle-import:DIL16")
      (libsource (lib "eagle-import") (part "8R-P"))
    )
    (comp (ref "RN2")
      (value "10K")
      (footprint "eagle-import:SIL9")
      (libsource (lib "eagle-import") (part "G08R"))
    )
    (comp (ref "RN3")
      (value "8R-P")
      (footprint "eagle-import:DIL16")
      (libsource (lib "eagle-import") (part "8R-P"))
    )
    (comp (ref "RN4")
      (value "10K")
      (footprint "eagle-import:SIL9")
      (libsource (lib "eagle-import") (part "G08R"))
    )
    (comp (ref "SJ1")
      (value "SJRND2")
      (footprint "eagle-import:SJ_RND2")
      (libsource (lib "eagle-import") (part "SJRND2"))
    )
    (comp (ref "SJ2")
      (value "SJRND2")
      (footprint "eagle-import:SJ_RND2")
      (libsource (lib "eagle-import") (part "SJRND2"))
    )
    (comp (ref "SJ3")
      (value "SJ-C")
      (footprint "eagle-import:SJW-C")
      (libsource (lib "eagle-import") (part "SJ-C"))
    )
    (comp (ref "SJ4")
      (value "SJRND2")
      (footprint "eagle-import:SJ_RND2")
      (libsource (lib "eagle-import") (part "SJRND2"))
    )
    (comp (ref "SJ5")
      (value "SJRND2")
      (footprint "eagle-import:SJ_RND2")
      (libsource (lib "eagle-import") (part "SJRND2"))
    )
    (comp (ref "SJ6")
      (value "SJRND2")
      (footprint "eagle-import:SJ_RND2")
      (libsource (lib "eagle-import") (part "SJRND2"))
    )
    (comp (ref "SJ7")
      (value "SJRND2")
      (footprint "eagle-import:SJ_RND2")
      (libsource (lib "eagle-import") (part "SJRND2"))
    )
    (comp (ref "SJ8")
      (value "SJRND2")
      (footprint "eagle-import:SJ_RND2")
      (libsource (lib "eagle-import") (part "SJRND2"))
    )
    (comp (ref "SJ9")
      (value "SJ-C")
      (footprint "eagle-import:SJW-C")
      (libsource (lib "eagle-import") (part "SJ-C"))
    )
    (comp (ref "SJ10")
      (value "SJRND2")
      (footprint "eagle-import:SJ_RND2")
      (libsource (lib "eagle-import") (part "SJRND2"))
    )
    (comp (ref "SJ11")
      (value "SJRND2")
      (footprint "eagle-import:SJ_RND2")
      (libsource (lib "eagle-import") (part "SJRND2"))
    )
    (comp (ref "SJ12")
      (value "SJRND2")
      (footprint "eagle-import:SJ_RND2")
      (libsource (lib "eagle-import") (part "SJRND2"))
    )
    (comp (ref "SJ13")
      (value "SJRND2")
      (footprint "eagle-import:SJ_RND2")
      (libsource (lib "eagle-import") (part "SJRND2"))
    )
    (comp (ref "SJ14")
      (value "SJRND2")
      (footprint "eagle-import:SJ_RND2")
      (libsource (lib "eagle-import") (part "SJRND2"))
    )
    (comp (ref "SJ15")
      (value "SJ-C")
      (footprint "eagle-import:SJW-C")
      (libsource (lib "eagle-import") (part "SJ-C"))
    )
    (comp (ref "SJ16")
      (value "SJRND2")
      (footprint "eagle-import:SJ_RND2")
      (libsource (lib "eagle-import") (part "SJRND2"))
    )
    (comp (ref "SJ17")
      (value "SJRND2")
      (footprint "eagle-import:SJ_RND2")
      (libsource (lib "eagle-import") (part "SJRND2"))
    )
    (comp (ref "SJ18")
      (value "SJRND2")
      (footprint "eagle-import:SJ_RND2")
      (libsource (lib "eagle-import") (part "SJRND2"))
    )
    (comp (ref "U$1")
      (value "NUCLEO_64_GENERIC")
      (footprint "eagle-import:NUCLEO_BRD_BASE64")
      (libsource (lib "eagle-import") (part "NUCLEO_64_GENERIC"))
    )
    (comp (ref "U1")
      (value "74HC166")
      (footprint "eagle-import:DIL16")
      (libsource (lib "eagle-import") (part "74166N"))
    )
    (comp (ref "U2")
      (value "74HC166")
      (footprint "eagle-import:DIL16")
      (libsource (lib "eagle-import") (part "74166N"))
    )
    (comp (ref "U3")
      (value "TC4426APDIP")
      (footprint "eagle-import:DIL08-LONG")
      (libsource (lib "eagle-import") (part "TC4426APDIP"))
    )
    (comp (ref "U4")
      (value "TC4426APDIP")
      (footprint "eagle-import:DIL08-LONG")
      (libsource (lib "eagle-import") (part "TC4426APDIP"))
    )
    (comp (ref "U5")
      (value "TC4426APDIP")
      (footprint "eagle-import:DIL08-LONG")
      (libsource (lib "eagle-import") (part "TC4426APDIP"))
    )
    (comp (ref "U6")
      (value "TC4426APDIP")
      (footprint "eagle-import:DIL08-LONG")
      (libsource (lib "eagle-import") (part "TC4426APDIP"))
    )
    (comp (ref "U7")
      (value "CAN-TXR-PDIP")
      (footprint "eagle-import:DIL08")
      (libsource (lib "eagle-import") (part "PCA82C250"))
    )
    (comp (ref "U7B")
      (value "CAN-TXR-SO8")
      (footprint "eagle-import:SO-08")
      (libsource (lib "eagle-import") (part "MCP2551-SN"))
    )
    (comp (ref "U8")
      (value "AP1509")
      (footprint "eagle-import:SO-08")
      (libsource (lib "eagle-import") (part "AP1509"))
    )
    (comp (ref "U8B")
      (value "LM2574N-5.0")
      (footprint "eagle-import:DIL08")
      (libsource (lib "eagle-import") (part "LM2574?-N5.0"))
    )
    (comp (ref "U9")
      (value "LM324N")
      (footprint "eagle-import:DIL14")
      (libsource (lib "eagle-import") (part "LM324N"))
    )
    (comp (ref "U10")
      (value "LM324N")
      (footprint "eagle-import:DIL14")
      (libsource (lib "eagle-import") (part "LM324N"))
    )
    (comp (ref "U11")
      (value "74HCT595N")
      (footprint "eagle-import:DIL16")
      (libsource (lib "eagle-import") (part "74595NHCT"))
    )
    (comp (ref "U12")
      (value "ULN2803A")
      (footprint "eagle-import:DIL18-THIN")
      (libsource (lib "eagle-import") (part "ULN2803A"))
    )
    (comp (ref "X1")
      (value "CONNECTOR-M023.5MM-LOCK")
      (footprint "eagle-import:SCREWTERMINAL-3.5MM-2_LOCK")
      (libsource (lib "eagle-import") (part "CONNECTOR-M023.5MM-LOCK"))
    )
  )
  (nets
    (net (code "1") (name "+3V3") (class "Default")
      (node (ref "C11") (pin "1") (pinfunction "1_1") (pintype "passive"))
      (node (ref "C4") (pin "1") (pinfunction "1_1") (pintype "passive"))
      (node (ref "R1") (pin "2") (pinfunction "2_2") (pintype "passive"))
      (node (ref "R45") (pin "1") (pinfunction "1_1") (pintype "passive"))
      (node (ref "R46") (pin "2") (pinfunction "2_2") (pintype "passive"))
      (node (ref "R47") (pin "2") (pinfunction "2_2") (pintype "passive"))
      (node (ref "R48") (pin "2") (pinfunction "2_2") (pintype "passive"))
      (node (ref "R49") (pin "2") (pinfunction "2_2") (pintype "passive"))
      (node (ref "R50") (pin "2") (pinfunction "2_2") (pintype "passive"))
      (node (ref "R51") (pin "2") (pinfunction "2_2") (pintype "passive"))
      (node (ref "R52") (pin "2") (pinfunction "2_2") (pintype "passive"))
      (node (ref "R53") (pin "1") (pinfunction "1_1") (pintype "passive"))
      (node (ref "R54") (pin "1") (pinfunction "1_1") (pintype "passive"))
      (node (ref "R55") (pin "1") (pinfunction "1_1") (pintype "passive"))
      (node (ref "R56") (pin "1") (pinfunction "1_1") (pintype "passive"))
      (node (ref "R57") (pin "1") (pinfunction "1_1") (pintype "passive"))
      (node (ref "R58") (pin "1") (pinfunction "1_1") (pintype "passive"))
      (node (ref "R59") (pin "1") (pinfunction "1_1") (pintype "passive"))
      (node (ref "R60") (pin "1") (pinfunction "1_1") (pintype "passive"))
      (node (ref "RN2") (pin "1") (pinfunction "1_1") (pintype "passive"))
      (node (ref "RN4") (pin "1") (pinfunction "1_1") (pintype "passive"))
      (node (ref "SJ18") (pin "P$1") (pinfunction "1_P$1") (pintype "passive"))
      (node (ref "U$1") (pin "3V3") (pinfunction "3V3_3V3") (pintype "power_in"))
      (node (ref "U1") (pin "1") (pinfunction "SER_1") (pintype "input"))
      (node (ref "U1") (pin "16") (pinfunction "VCC_16") (pintype "power_in"))
      (node (ref "U1") (pin "9") (pinfunction "CLR_9") (pintype "input"))
      (node (ref "U2") (pin "16") (pinfunction "VCC_16") (pintype "power_in"))
      (node (ref "U2") (pin "9") (pinfunction "CLR_9") (pintype "input"))
    )
    (net (code "2") (name "+5V") (class "Default")
      (node (ref "C3") (pin "1") (pinfunction "1_1") (pintype "passive"))
      (node (ref "C5") (pin "1") (pinfunction "1_1") (pintype "passive"))
      (node (ref "C8") (pin "1") (pinfunction "1_1") (pintype "passive"))
      (node (ref "C9") (pin "1") (pinfunction "1_1") (pintype "passive"))
      (node (ref "IC3") (pin "10") (pinfunction "SCL_10") (pintype "input"))
      (node (ref "IC3") (pin "16") (pinfunction "VCC_16") (pintype "power_in"))
      (node (ref "JP10") (pin "2") (pinfunction "2_2") (pintype "passive"))
      (node (ref "JP11") (pin "3") (pinfunction "3_3") (pintype "passive"))
      (node (ref "JP11") (pin "4") (pinfunction "4_4") (pintype "passive"))
      (node (ref "JP12") (pin "3") (pinfunction "3_3") (pintype "passive"))
      (node (ref "JP12") (pin "4") (pinfunction "4_4") (pintype "passive"))
      (node (ref "JP16") (pin "3") (pinfunction "3_3") (pintype "passive"))
      (node (ref "JP16") (pin "4") (pinfunction "4_4") (pintype "passive"))
      (node (ref "JP7") (pin "3") (pinfunction "3_3") (pintype "passive"))
      (node (ref "JP7") (pin "4") (pinfunction "4_4") (pintype "passive"))
      (node (ref "JP8") (pin "3") (pinfunction "3_3") (pintype "passive"))
      (node (ref "PORTA") (pin "6") (pinfunction "6_6") (pintype "passive"))
      (node (ref "PORTB") (pin "6") (pinfunction "6_6") (pintype "passive"))
      (node (ref "PORTC") (pin "6") (pinfunction "6_6") (pintype "passive"))
      (node (ref "R19") (pin "2") (pinfunction "2_2") (pintype "passive"))
      (node (ref "R20") (pin "2") (pinfunction "2_2") (pintype "passive"))
      (node (ref "R21") (pin "2") (pinfunction "2_2") (pintype "passive"))
      (node (ref "R22") (pin "1") (pinfunction "1_1") (pintype "passive"))
      (node (ref "R23") (pin "1") (pinfunction "1_1") (pintype "passive"))
      (node (ref "R24") (pin "1") (pinfunction "1_1") (pintype "passive"))
      (node (ref "R25") (pin "1") (pinfunction "1_1") (pintype "passive"))
      (node (ref "R26") (pin "1") (pinfunction "1_1") (pintype "passive"))
      (node (ref "R27") (pin "1") (pinfunction "1_1") (pintype "passive"))
      (node (ref "R62") (pin "1") (pinfunction "1_1") (pintype "passive"))
      (node (ref "R63") (pin "1") (pinfunction "1_1") (pintype "passive"))
      (node (ref "R64") (pin "1") (pinfunction "1_1") (pintype "passive"))
      (node (ref "R65") (pin "1") (pinfunction "1_1") (pintype "passive"))
      (node (ref "R66") (pin "1") (pinfunction "1_1") (pintype "passive"))
      (node (ref "R67") (pin "1") (pinfunction "1_1") (pintype "passive"))
      (node (ref "SJ1") (pin "P$2") (pinfunction "2_P$2") (pintype "passive"))
      (node (ref "SJ10") (pin "P$2") (pinfunction "2_P$2") (pintype "passive"))
      (node (ref "SJ4") (pin "P$2") (pinfunction "2_P$2") (pintype "passive"))
      (node (ref "SJ7") (pin "P$2") (pinfunction "2_P$2") (pintype "passive"))
      (node (ref "U$1") (pin "5V2") (pinfunction "5V2_5V2") (pintype "power_in"))
      (node (ref "U11") (pin "10") (pinfunction "SCL_10") (pintype "input"))
      (node (ref "U11") (pin "16") (pinfunction "VCC_16") (pintype "power_in"))
      (node (ref "U7") (pin "3") (pinfunction "VCC_3") (pintype "power_in"))
      (node (ref "U7B") (pin "3") (pinfunction "VDD_3") (pintype "power_in"))
      (node (ref "X1") (pin "1") (pinfunction "1_1") (pintype "passive"))
    )
    (net (code "3") (name "+12V") (class "Default")
      (node (ref "C10") (pin "1") (pinfunction "1_1") (pintype "passive"))
      (node (ref "C6") (pin "1") (pinfunction "1_1") (pintype "passive"))
      (node (ref "C7") (pin "1") (pinfunction "1_1") (pintype "passive"))
      (node (ref "J3") (pin "1") (pinfunction "1_1") (pintype "passive"))
      (node (ref "JP10") (pin "3") (pinfunction "3_3") (pintype "passive"))
      (node (ref "JP4") (pin "2") (pinfunction "2_2") (pintype "passive"))
      (node (ref "SJ11") (pin "P$2") (pinfunction "2_P$2") (pintype "passive"))
      (node (ref "SJ14") (pin "P$2") (pinfunction "2_P$2") (pintype "passive"))
      (node (ref "SJ2") (pin "P$2") (pinfunction "2_P$2") (pintype "passive"))
      (node (ref "SJ5") (pin "P$2") (pinfunction "2_P$2") (pintype "passive"))
      (node (ref "SJ8") (pin "P$2") (pinfunction "2_P$2") (pintype "passive"))
      (node (ref "U10") (pin "4") (pinfunction "V+_4") (pintype "power_in"))
      (node (ref "U3") (pin "6") (pinfunction "VDD_6") (pintype "power_in"))
      (node (ref "U4") (pin "6") (pinfunction "VDD_6") (pintype "power_in"))
      (node (ref "U5") (pin "6") (pinfunction "VDD_6") (pintype "power_in"))
      (node (ref "U6") (pin "6") (pinfunction "VDD_6") (pintype "power_in"))
      (node (ref "U8") (pin "1") (pinfunction "VIN_1") (pintype "bidirectional"))
      (node (ref "U8B") (pin "5") (pinfunction "IN_5") (pintype "input"))
      (node (ref "U9") (pin "4") (pinfunction "V+_4") (pintype "power_in"))
    )
    (net (code "4") (name "/AGND") (class "Default")
      (node (ref "U$1") (pin "AGND") (pinfunction "AGND_AGND") (pintype "power_in"))
    )
    (net (code "5") (name "/AVDD") (class "Default")
      (node (ref "U$1") (pin "AVDD") (pinfunction "AVDD_AVDD") (pintype "power_in"))
    )
    (net (code "6") (name "/CANH") (class "Default")
      (node (ref "J1") (pin "1") (pinfunction "1_1") (pintype "passive"))
      (node (ref "J2") (pin "1") (pinfunction "1_1") (pintype "passive"))
      (node (ref "U7") (pin "7") (pinfunction "CANH_7") (pintype "bidirectional"))
      (node (ref "U7B") (pin "7") (pinfunction "CANH_7") (pintype "bidirectional"))
    )
    (net (code "7") (name "/CANL") (class "Default")
      (node (ref "J1") (pin "2") (pinfunction "2_2") (pintype "passive"))
      (node (ref "J2") (pin "2") (pinfunction "2_2") (pintype "passive"))
      (node (ref "U7") (pin "6") (pinfunction "CANL_6") (pintype "bidirectional"))
      (node (ref "U7B") (pin "6") (pinfunction "CANL_6") (pintype "bidirectional"))
    )
    (net (code "8") (name "/GND4") (class "Default")
      (node (ref "U$1") (pin "GND4") (pinfunction "GND4_GND4") (pintype "power_in"))
    )
    (net (code "9") (name "/PWR_POS") (class "Default")
      (node (ref "J1") (pin "8") (pinfunction "8_8") (pintype "passive"))
      (node (ref "J2") (pin "8") (pinfunction "8_8") (pintype "passive"))
      (node (ref "R40") (pin "1") (pinfunction "1_1") (pintype "passive"))
    )
    (net (code "10") (name "/U5V") (class "Default")
      (node (ref "U$1") (pin "U5V") (pinfunction "U5V_U5V") (pintype "power_in"))
    )
    (net (code "11") (name "/VBAT") (class "Default")
      (node (ref "U$1") (pin "VBAT") (pinfunction "VBAT_VBAT") (pintype "power_in"))
    )
    (net (code "12") (name "/VDD") (class "Default")
      (node (ref "U$1") (pin "VDD") (pinfunction "VDD_VDD") (pintype "power_in"))
    )
    (net (code "13") (name "CANRX") (class "Default")
      (node (ref "U$1") (pin "PB8") (pinfunction "PB8_PB8") (pintype "bidirectional"))
      (node (ref "U7") (pin "4") (pinfunction "RXD_4") (pintype "output"))
      (node (ref "U7B") (pin "4") (pinfunction "RXD_4") (pintype "bidirectional"))
    )
    (net (code "14") (name "CANTX") (class "Default")
      (node (ref "U$1") (pin "PB9") (pinfunction "PB9_PB9") (pintype "bidirectional"))
      (node (ref "U7") (pin "1") (pinfunction "TXD_1") (pintype "input"))
      (node (ref "U7B") (pin "1") (pinfunction "TXD_1") (pintype "bidirectional"))
    )
    (net (code "15") (name "E_CS") (class "Default")
      (node (ref "JP9") (pin "4") (pinfunction "4_4") (pintype "passive"))
      (node (ref "R23") (pin "2") (pinfunction "2_2") (pintype "passive"))
      (node (ref "U$1") (pin "PC10") (pinfunction "PC10_PC10") (pintype "bidirectional"))
    )
    (net (code "16") (name "E_LAT") (class "Default")
      (node (ref "JP10") (pin "1") (pinfunction "1_1") (pintype "passive"))
      (node (ref "R22") (pin "2") (pinfunction "2_2") (pintype "passive"))
      (node (ref "U$1") (pin "PC11") (pinfunction "PC11_PC11") (pintype "bidirectional"))
    )
    (net (code "17") (name "GND") (class "Default")
      (node (ref "C1") (pin "2") (pinfunction "2_2") (pintype "passive"))
      (node (ref "C10") (pin "2") (pinfunction "2_2") (pintype "passive"))
      (node (ref "C11") (pin "2") (pinfunction "2_2") (pintype "passive"))
      (node (ref "C2") (pin "-") (pinfunction "-_-") (pintype "passive"))
      (node (ref "C3") (pin "2") (pinfunction "2_2") (pintype "passive"))
      (node (ref "C4") (pin "2") (pinfunction "2_2") (pintype "passive"))
      (node (ref "C5") (pin "2") (pinfunction "2_2") (pintype "passive"))
      (node (ref "C6") (pin "2") (pinfunction "2_2") (pintype "passive"))
      (node (ref "C7") (pin "2") (pinfunction "2_2") (pintype "passive"))
      (node (ref "C8") (pin "2") (pinfunction "2_2") (pintype "passive"))
      (node (ref "C9") (pin "2") (pinfunction "2_2") (pintype "passive"))
      (node (ref "D1") (pin "A") (pinfunction "A_A") (pintype "passive"))
      (node (ref "IC3") (pin "13") (pinfunction "G_13") (pintype "input"))
      (node (ref "IC3") (pin "8") (pinfunction "GND_8") (pintype "power_in"))
      (node (ref "J1") (pin "3") (pinfunction "3_3") (pintype "passive"))
      (node (ref "J1") (pin "6") (pinfunction "6_6") (pintype "passive"))
      (node (ref "J1") (pin "7") (pinfunction "7_7") (pintype "passive"))
      (node (ref "J2") (pin "3") (pinfunction "3_3") (pintype "passive"))
      (node (ref "J2") (pin "6") (pinfunction "6_6") (pintype "passive"))
      (node (ref "J2") (pin "7") (pinfunction "7_7") (pintype "passive"))
      (node (ref "J3") (pin "2") (pinfunction "2_2") (pintype "passive"))
      (node (ref "J3") (pin "3") (pinfunction "3_3") (pintype "passive"))
      (node (ref "JP10") (pin "4") (pinfunction "4_4") (pintype "passive"))
      (node (ref "JP11") (pin "5") (pinfunction "5_5") (pintype "passive"))
      (node (ref "JP11") (pin "6") (pinfunction "6_6") (pintype "passive"))
      (node (ref "JP12") (pin "5") (pinfunction "5_5") (pintype "passive"))
      (node (ref "JP12") (pin "6") (pinfunction "6_6") (pintype "passive"))
      (node (ref "JP16") (pin "5") (pinfunction "5_5") (pintype "passive"))
      (node (ref "JP16") (pin "6") (pinfunction "6_6") (pintype "passive"))
      (node (ref "JP7") (pin "5") (pinfunction "5_5") (pintype "passive"))
      (node (ref "JP7") (pin "6") (pinfunction "6_6") (pintype "passive"))
      (node (ref "JP8") (pin "4") (pinfunction "4_4") (pintype "passive"))
      (node (ref "PORTA") (pin "5") (pinfunction "5_5") (pintype "passive"))
      (node (ref "PORTB") (pin "5") (pinfunction "5_5") (pintype "passive"))
      (node (ref "PORTC") (pin "5") (pinfunction "5_5") (pintype "passive"))
      (node (ref "Q1") (pin "2") (pinfunction "S_2") (pintype "passive"))
      (node (ref "Q10") (pin "2") (pinfunction "S_2") (pintype "passive"))
      (node (ref "Q11") (pin "2") (pinfunction "S_2") (pintype "passive"))
      (node (ref "Q12") (pin "2") (pinfunction "S_2") (pintype "passive"))
      (node (ref "Q13") (pin "2") (pinfunction "S_2") (pintype "passive"))
      (node (ref "Q14") (pin "2") (pinfunction "S_2") (pintype "passive"))
      (node (ref "Q15") (pin "2") (pinfunction "S_2") (pintype "passive"))
      (node (ref "Q16") (pin "2") (pinfunction "S_2") (pintype "passive"))
      (node (ref "Q2") (pin "2") (pinfunction "S_2") (pintype "passive"))
      (node (ref "Q3") (pin "2") (pinfunction "S_2") (pintype "passive"))
      (node (ref "Q4") (pin "2") (pinfunction "S_2") (pintype "passive"))
      (node (ref "Q5") (pin "2") (pinfunction "S_2") (pintype "passive"))
      (node (ref "Q6") (pin "2") (pinfunction "S_2") (pintype "passive"))
      (node (ref "Q7") (pin "2") (pinfunction "S_2") (pintype "passive"))
      (node (ref "Q8") (pin "2") (pinfunction "S_2") (pintype "passive"))
      (node (ref "Q9") (pin "2") (pinfunction "S_2") (pintype "passive"))
      (node (ref "R2") (pin "1") (pinfunction "1_1") (pintype "passive"))
      (node (ref "R61") (pin "2") (pinfunction "2_2") (pintype "passive"))
      (node (ref "SJ12") (pin "P$2") (pinfunction "2_P$2") (pintype "passive"))
      (node (ref "SJ3") (pin "2") (pinfunction "2_2") (pintype "passive"))
      (node (ref "SJ6") (pin "P$2") (pinfunction "2_P$2") (pintype "passive"))
      (node (ref "SJ9") (pin "2") (pinfunction "2_2") (pintype "passive"))
      (node (ref "U$1") (pin "GND3") (pinfunction "GND3_GND3") (pintype "power_in"))
      (node (ref "U$1") (pin "GND5") (pinfunction "GND5_GND5") (pintype "power_in"))
      (node (ref "U$1") (pin "GND6") (pinfunction "GND6_GND6") (pintype "power_in"))
      (node (ref "U$1") (pin "GND7") (pinfunction "GND7_GND7") (pintype "power_in"))
      (node (ref "U$1") (pin "GND8") (pinfunction "GND8_GND8") (pintype "power_in"))
      (node (ref "U1") (pin "6") (pinfunction "INH_6") (pintype "input"))
      (node (ref "U1") (pin "8") (pinfunction "GND_8") (pintype "power_in"))
      (node (ref "U10") (pin "11") (pinfunction "V-_11") (pintype "power_in"))
      (node (ref "U11") (pin "13") (pinfunction "G_13") (pintype "input"))
      (node (ref "U11") (pin "8") (pinfunction "GND_8") (pintype "power_in"))
      (node (ref "U2") (pin "6") (pinfunction "INH_6") (pintype "input"))
      (node (ref "U2") (pin "8") (pinfunction "GND_8") (pintype "power_in"))
      (node (ref "U3") (pin "3") (pinfunction "VSS_3") (pintype "power_in"))
      (node (ref "U4") (pin "3") (pinfunction "VSS_3") (pintype "power_in"))
      (node (ref "U5") (pin "3") (pinfunction "VSS_3") (pintype "power_in"))
      (node (ref "U6") (pin "3") (pinfunction "VSS_3") (pintype "power_in"))
      (node (ref "U7") (pin "2") (pinfunction "GND_2") (pintype "power_in"))
      (node (ref "U7B") (pin "2") (pinfunction "VSS_2") (pintype "power_in"))
      (node (ref "U8") (pin "4") (pinfunction "SD_4") (pintype "bidirectional"))
      (node (ref "U8") (pin "5") (pinfunction "GND1_5") (pintype "power_in"))
      (node (ref "U8") (pin "6") (pinfunction "GND2_6") (pintype "power_in"))
      (node (ref "U8") (pin "7") (pinfunction "GND3_7") (pintype "power_in"))
      (node (ref "U8") (pin "8") (pinfunction "GND4_8") (pintype "power_in"))
      (node (ref "U8B") (pin "2") (pinfunction "GNDSIG_2") (pintype "input"))
      (node (ref "U8B") (pin "3") (pinfunction "~{ON/OFF}_3") (pintype "input"))
      (node (ref "U8B") (pin "4") (pinfunction "GND_4") (pintype "power_in"))
      (node (ref "U9") (pin "11") (pinfunction "V-_11") (pintype "power_in"))
      (node (ref "X1") (pin "2") (pinfunction "2_2") (pintype "passive"))
    )
    (net (code "18") (name "I2CSCL") (class "Default")
      (node (ref "JP8") (pin "2") (pinfunction "2_2") (pintype "passive"))
      (node (ref "R63") (pin "2") (pinfunction "2_2") (pintype "passive"))
      (node (ref "U$1") (pin "PB6") (pinfunction "PB6_PB6") (pintype "bidirectional"))
    )
    (net (code "19") (name "I2CSDA") (class "Default")
      (node (ref "JP8") (pin "1") (pinfunction "1_1") (pintype "passive"))
      (node (ref "R62") (pin "2") (pinfunction "2_2") (pintype "passive"))
      (node (ref "U$1") (pin "PB7") (pinfunction "PB7_PB7") (pintype "bidirectional"))
    )
    (net (code "20") (name "ILAT") (class "Default")
      (node (ref "U$1") (pin "PA6") (pinfunction "PA6_PA6") (pintype "bidirectional"))
      (node (ref "U1") (pin "15") (pinfunction "SH/~{LD}_15") (pintype "input"))
      (node (ref "U2") (pin "15") (pinfunction "SH/~{LD}_15") (pintype "input"))
    )
    (net (code "21") (name "MISO") (class "Default")
      (node (ref "JP9") (pin "1") (pinfunction "1_1") (pintype "passive"))
      (node (ref "U$1") (pin "PB4") (pinfunction "PB4_PB4") (pintype "bidirectional"))
    )
    (net (code "22") (name "MISO2") (class "Default")
      (node (ref "SJ13") (pin "P$2") (pinfunction "2_P$2") (pintype "passive"))
      (node (ref "U$1") (pin "PC2") (pinfunction "PC2_PC2") (pintype "bidirectional"))
      (node (ref "U2") (pin "13") (pinfunction "QH_13") (pintype "output"))
    )
    (net (code "23") (name "MOSI") (class "Default")
      (node (ref "R20") (pin "1") (pinfunction "1_1") (pintype "passive"))
      (node (ref "SJ15") (pin "1") (pinfunction "1_1") (pintype "passive"))
      (node (ref "SJ17") (pin "P$2") (pinfunction "2_P$2") (pintype "passive"))
      (node (ref "U$1") (pin "PB5") (pinfunction "PB5_PB5") (pintype "bidirectional"))
      (node (ref "U11") (pin "14") (pinfunction "SER_14") (pintype "input"))
    )
    (net (code "24") (name "Net-(D2-PadA)") (class "Default")
      (node (ref "D2") (pin "A") (pinfunction "A_A") (pintype "passive"))
      (node (ref "JP4") (pin "4") (pinfunction "4_4") (pintype "passive"))
    )
    (net (code "25") (name "Net-(D2-PadC)") (class "Default")
      (node (ref "D2") (pin "C") (pinfunction "C_C") (pintype "passive"))
      (node (ref "JP4") (pin "1") (pinfunction "1_1") (pintype "passive"))
    )
    (net (code "26") (name "Net-(IC3A-QA)") (class "Default")
      (node (ref "IC3") (pin "15") (pinfunction "QA_15") (pintype "tri_state"))
      (node (ref "IC8") (pin "1") (pinfunction "I1_1") (pintype "input"))
      (node (ref "R11") (pin "1") (pinfunction "1_1") (pintype "passive"))
    )
    (net (code "27") (name "Net-(IC3A-QB)") (class "Default")
      (node (ref "IC3") (pin "1") (pinfunction "QB_1") (pintype "tri_state"))
      (node (ref "IC8") (pin "2") (pinfunction "I2_2") (pintype "input"))
      (node (ref "R12") (pin "1") (pinfunction "1_1") (pintype "passive"))
    )
    (net (code "28") (name "Net-(IC3A-QC)") (class "Default")
      (node (ref "IC3") (pin "2") (pinfunction "QC_2") (pintype "tri_state"))
      (node (ref "IC8") (pin "3") (pinfunction "I3_3") (pintype "input"))
      (node (ref "R13") (pin "1") (pinfunction "1_1") (pintype "passive"))
    )
    (net (code "29") (name "Net-(IC3A-QD)") (class "Default")
      (node (ref "IC3") (pin "3") (pinfunction "QD_3") (pintype "tri_state"))
      (node (ref "IC8") (pin "4") (pinfunction "I4_4") (pintype "input"))
      (node (ref "R14") (pin "1") (pinfunction "1_1") (pintype "passive"))
    )
    (net (code "30") (name "Net-(IC3A-QE)") (class "Default")
      (node (ref "IC3") (pin "4") (pinfunction "QE_4") (pintype "tri_state"))
      (node (ref "IC8") (pin "5") (pinfunction "I5_5") (pintype "input"))
      (node (ref "R15") (pin "1") (pinfunction "1_1") (pintype "passive"))
    )
    (net (code "31") (name "Net-(IC3A-QF)") (class "Default")
      (node (ref "IC3") (pin "5") (pinfunction "QF_5") (pintype "tri_state"))
      (node (ref "IC8") (pin "6") (pinfunction "I6_6") (pintype "input"))
      (node (ref "R16") (pin "1") (pinfunction "1_1") (pintype "passive"))
    )
    (net (code "32") (name "Net-(IC3A-QG)") (class "Default")
      (node (ref "IC3") (pin "6") (pinfunction "QG_6") (pintype "tri_state"))
      (node (ref "IC8") (pin "7") (pinfunction "I7_7") (pintype "input"))
      (node (ref "R17") (pin "1") (pinfunction "1_1") (pintype "passive"))
    )
    (net (code "33") (name "Net-(IC3A-QH)") (class "Default")
      (node (ref "IC3") (pin "7") (pinfunction "QH_7") (pintype "tri_state"))
      (node (ref "IC8") (pin "8") (pinfunction "I8_8") (pintype "input"))
      (node (ref "R18") (pin "1") (pinfunction "1_1") (pintype "passive"))
    )
    (net (code "34") (name "Net-(IC8-CD+)") (class "Default")
      (node (ref "IC8") (pin "10") (pinfunction "CD+_10") (pintype "passive"))
      (node (ref "SJ10") (pin "P$1") (pinfunction "1_P$1") (pintype "passive"))
      (node (ref "SJ11") (pin "P$1") (pinfunction "1_P$1") (pintype "passive"))
      (node (ref "SJ12") (pin "P$1") (pinfunction "1_P$1") (pintype "passive"))
    )
    (net (code "35") (name "Net-(IC8-GND)") (class "Default")
      (node (ref "IC8") (pin "9") (pinfunction "GND_9") (pintype "power_in"))
      (node (ref "SJ7") (pin "P$1") (pinfunction "1_P$1") (pintype "passive"))
      (node (ref "SJ8") (pin "P$1") (pinfunction "1_P$1") (pintype "passive"))
      (node (ref "SJ9") (pin "1") (pinfunction "1_1") (pintype "passive"))
    )
    (net (code "36") (name "Net-(IC8-O1)") (class "Default")
      (node (ref "IC8") (pin "18") (pinfunction "O1_18") (pintype "open_collector"))
      (node (ref "JP6") (pin "1") (pinfunction "1_1") (pintype "passive"))
      (node (ref "Q9") (pin "3") (pinfunction "D_3") (pintype "passive"))
    )
    (net (code "37") (name "Net-(IC8-O2)") (class "Default")
      (node (ref "IC8") (pin "17") (pinfunction "O2_17") (pintype "open_collector"))
      (node (ref "JP6") (pin "2") (pinfunction "2_2") (pintype "passive"))
      (node (ref "Q10") (pin "3") (pinfunction "D_3") (pintype "passive"))
    )
    (net (code "38") (name "Net-(IC8-O3)") (class "Default")
      (node (ref "IC8") (pin "16") (pinfunction "O3_16") (pintype "open_collector"))
      (node (ref "JP6") (pin "3") (pinfunction "3_3") (pintype "passive"))
      (node (ref "Q11") (pin "3") (pinfunction "D_3") (pintype "passive"))
    )
    (net (code "39") (name "Net-(IC8-O4)") (class "Default")
      (node (ref "IC8") (pin "15") (pinfunction "O4_15") (pintype "open_collector"))
      (node (ref "JP6") (pin "4") (pinfunction "4_4") (pintype "passive"))
      (node (ref "Q12") (pin "3") (pinfunction "D_3") (pintype "passive"))
    )
    (net (code "40") (name "Net-(IC8-O5)") (class "Default")
      (node (ref "IC8") (pin "14") (pinfunction "O5_14") (pintype "open_collector"))
      (node (ref "JP6") (pin "5") (pinfunction "5_5") (pintype "passive"))
      (node (ref "Q13") (pin "3") (pinfunction "D_3") (pintype "passive"))
    )
    (net (code "41") (name "Net-(IC8-O6)") (class "Default")
      (node (ref "IC8") (pin "13") (pinfunction "O6_13") (pintype "open_collector"))
      (node (ref "JP6") (pin "6") (pinfunction "6_6") (pintype "passive"))
      (node (ref "Q14") (pin "3") (pinfunction "D_3") (pintype "passive"))
    )
    (net (code "42") (name "Net-(IC8-O7)") (class "Default")
      (node (ref "IC8") (pin "12") (pinfunction "O7_12") (pintype "open_collector"))
      (node (ref "JP6") (pin "7") (pinfunction "7_7") (pintype "passive"))
      (node (ref "Q15") (pin "3") (pinfunction "D_3") (pintype "passive"))
    )
    (net (code "43") (name "Net-(IC8-O8)") (class "Default")
      (node (ref "IC8") (pin "11") (pinfunction "O8_11") (pintype "open_collector"))
      (node (ref "JP6") (pin "8") (pinfunction "8_8") (pintype "passive"))
      (node (ref "Q16") (pin "3") (pinfunction "D_3") (pintype "passive"))
    )
    (net (code "44") (name "Net-(J1-Pad4)") (class "Default")
      (node (ref "J1") (pin "4") (pinfunction "4_4") (pintype "passive"))
      (node (ref "J2") (pin "4") (pinfunction "4_4") (pintype "passive"))
    )
    (net (code "45") (name "Net-(J1-Pad5)") (class "Default")
      (node (ref "J1") (pin "5") (pinfunction "5_5") (pintype "passive"))
      (node (ref "J2") (pin "5") (pinfunction "5_5") (pintype "passive"))
    )
    (net (code "46") (name "Net-(JP2-Pad1)") (class "Default")
      (node (ref "JP2") (pin "1") (pinfunction "1_1") (pintype "passive"))
      (node (ref "PORTB") (pin "1") (pinfunction "1_1") (pintype "passive"))
      (node (ref "R35") (pin "2") (pinfunction "2_2") (pintype "passive"))
      (node (ref "R45") (pin "2") (pinfunction "2_2") (pintype "passive"))
      (node (ref "RN1") (pin "1") (pinfunction "1_1") (pintype "passive"))
      (node (ref "RN2") (pin "9") (pinfunction "9_9") (pintype "passive"))
    )
    (net (code "47") (name "Net-(JP3-Pad1)") (class "Default")
      (node (ref "JP3") (pin "1") (pinfunction "1_1") (pintype "passive"))
      (node (ref "PORTA") (pin "1") (pinfunction "1_1") (pintype "passive"))
      (node (ref "R44") (pin "2") (pinfunction "2_2") (pintype "passive"))
      (node (ref "R53") (pin "2") (pinfunction "2_2") (pintype "passive"))
      (node (ref "RN3") (pin "1") (pinfunction "1_1") (pintype "passive"))
      (node (ref "RN4") (pin "9") (pinfunction "9_9") (pintype "passive"))
    )
    (net (code "48") (name "Net-(JP4-Pad3)") (class "Default")
      (node (ref "JP4") (pin "3") (pinfunction "3_3") (pintype "passive"))
      (node (ref "R40") (pin "2") (pinfunction "2_2") (pintype "passive"))
    )
    (net (code "49") (name "Net-(Q1-D)") (class "Default")
      (node (ref "JP1") (pin "1") (pinfunction "1_1") (pintype "passive"))
      (node (ref "Q1") (pin "3") (pinfunction "D_3") (pintype "passive"))
      (node (ref "U12") (pin "18") (pinfunction "O1_18") (pintype "open_collector"))
    )
    (net (code "50") (name "Net-(Q1-G)") (class "Default")
      (node (ref "Q1") (pin "1") (pinfunction "G_1") (pintype "passive"))
      (node (ref "R3") (pin "2") (pinfunction "2_2") (pintype "passive"))
    )
    (net (code "51") (name "Net-(Q2-D)") (class "Default")
      (node (ref "JP1") (pin "2") (pinfunction "2_2") (pintype "passive"))
      (node (ref "Q2") (pin "3") (pinfunction "D_3") (pintype "passive"))
      (node (ref "U12") (pin "17") (pinfunction "O2_17") (pintype "open_collector"))
    )
    (net (code "52") (name "Net-(Q2-G)") (class "Default")
      (node (ref "Q2") (pin "1") (pinfunction "G_1") (pintype "passive"))
      (node (ref "R4") (pin "2") (pinfunction "2_2") (pintype "passive"))
    )
    (net (code "53") (name "Net-(Q3-D)") (class "Default")
      (node (ref "JP1") (pin "3") (pinfunction "3_3") (pintype "passive"))
      (node (ref "Q3") (pin "3") (pinfunction "D_3") (pintype "passive"))
      (node (ref "U12") (pin "16") (pinfunction "O3_16") (pintype "open_collector"))
    )
    (net (code "54") (name "Net-(Q3-G)") (class "Default")
      (node (ref "Q3") (pin "1") (pinfunction "G_1") (pintype "passive"))
      (node (ref "R5") (pin "2") (pinfunction "2_2") (pintype "passive"))
    )
    (net (code "55") (name "Net-(Q4-D)") (class "Default")
      (node (ref "JP1") (pin "4") (pinfunction "4_4") (pintype "passive"))
      (node (ref "Q4") (pin "3") (pinfunction "D_3") (pintype "passive"))
      (node (ref "U12") (pin "15") (pinfunction "O4_15") (pintype "open_collector"))
    )
    (net (code "56") (name "Net-(Q4-G)") (class "Default")
      (node (ref "Q4") (pin "1") (pinfunction "G_1") (pintype "passive"))
      (node (ref "R6") (pin "2") (pinfunction "2_2") (pintype "passive"))
    )
    (net (code "57") (name "Net-(Q5-D)") (class "Default")
      (node (ref "JP1") (pin "5") (pinfunction "5_5") (pintype "passive"))
      (node (ref "Q5") (pin "3") (pinfunction "D_3") (pintype "passive"))
      (node (ref "U12") (pin "14") (pinfunction "O5_14") (pintype "open_collector"))
    )
    (net (code "58") (name "Net-(Q5-G)") (class "Default")
      (node (ref "Q5") (pin "1") (pinfunction "G_1") (pintype "passive"))
      (node (ref "R7") (pin "2") (pinfunction "2_2") (pintype "passive"))
    )
    (net (code "59") (name "Net-(Q6-D)") (class "Default")
      (node (ref "JP1") (pin "6") (pinfunction "6_6") (pintype "passive"))
      (node (ref "Q6") (pin "3") (pinfunction "D_3") (pintype "passive"))
      (node (ref "U12") (pin "13") (pinfunction "O6_13") (pintype "open_collector"))
    )
    (net (code "60") (name "Net-(Q6-G)") (class "Default")
      (node (ref "Q6") (pin "1") (pinfunction "G_1") (pintype "passive"))
      (node (ref "R8") (pin "2") (pinfunction "2_2") (pintype "passive"))
    )
    (net (code "61") (name "Net-(Q7-D)") (class "Default")
      (node (ref "JP1") (pin "7") (pinfunction "7_7") (pintype "passive"))
      (node (ref "Q7") (pin "3") (pinfunction "D_3") (pintype "passive"))
      (node (ref "U12") (pin "12") (pinfunction "O7_12") (pintype "open_collector"))
    )
    (net (code "62") (name "Net-(Q7-G)") (class "Default")
      (node (ref "Q7") (pin "1") (pinfunction "G_1") (pintype "passive"))
      (node (ref "R9") (pin "2") (pinfunction "2_2") (pintype "passive"))
    )
    (net (code "63") (name "Net-(Q8-D)") (class "Default")
      (node (ref "JP1") (pin "8") (pinfunction "8_8") (pintype "passive"))
      (node (ref "Q8") (pin "3") (pinfunction "D_3") (pintype "passive"))
      (node (ref "U12") (pin "11") (pinfunction "O8_11") (pintype "open_collector"))
    )
    (net (code "64") (name "Net-(Q8-G)") (class "Default")
      (node (ref "Q8") (pin "1") (pinfunction "G_1") (pintype "passive"))
      (node (ref "R10") (pin "2") (pinfunction "2_2") (pintype "passive"))
    )
    (net (code "65") (name "Net-(Q9-G)") (class "Default")
      (node (ref "Q9") (pin "1") (pinfunction "G_1") (pintype "passive"))
      (node (ref "R11") (pin "2") (pinfunction "2_2") (pintype "passive"))
    )
    (net (code "66") (name "Net-(Q10-G)") (class "Default")
      (node (ref "Q10") (pin "1") (pinfunction "G_1") (pintype "passive"))
      (node (ref "R12") (pin "2") (pinfunction "2_2") (pintype "passive"))
    )
    (net (code "67") (name "Net-(Q11-G)") (class "Default")
      (node (ref "Q11") (pin "1") (pinfunction "G_1") (pintype "passive"))
      (node (ref "R13") (pin "2") (pinfunction "2_2") (pintype "passive"))
    )
    (net (code "68") (name "Net-(Q12-G)") (class "Default")
      (node (ref "Q12") (pin "1") (pinfunction "G_1") (pintype "passive"))
      (node (ref "R14") (pin "2") (pinfunction "2_2") (pintype "passive"))
    )
    (net (code "69") (name "Net-(Q13-G)") (class "Default")
      (node (ref "Q13") (pin "1") (pinfunction "G_1") (pintype "passive"))
      (node (ref "R15") (pin "2") (pinfunction "2_2") (pintype "passive"))
    )
    (net (code "70") (name "Net-(Q14-G)") (class "Default")
      (node (ref "Q14") (pin "1") (pinfunction "G_1") (pintype "passive"))
      (node (ref "R16") (pin "2") (pinfunction "2_2") (pintype "passive"))
    )
    (net (code "71") (name "Net-(Q15-G)") (class "Default")
      (node (ref "Q15") (pin "1") (pinfunction "G_1") (pintype "passive"))
      (node (ref "R17") (pin "2") (pinfunction "2_2") (pintype "passive"))
    )
    (net (code "72") (name "Net-(Q16-G)") (class "Default")
      (node (ref "Q16") (pin "1") (pinfunction "G_1") (pintype "passive"))
      (node (ref "R18") (pin "2") (pinfunction "2_2") (pintype "passive"))
    )
    (net (code "73") (name "Net-(RN1A-2)") (class "Default")
      (node (ref "R35") (pin "1") (pinfunction "1_1") (pintype "passive"))
      (node (ref "RN1") (pin "16") (pinfunction "2_16") (pintype "passive"))
      (node (ref "U2") (pin "14") (pinfunction "H_14") (pintype "input"))
    )
    (net (code "74") (name "Net-(RN1B-1)") (class "Default")
      (node (ref "JP2") (pin "2") (pinfunction "2_2") (pintype "passive"))
      (node (ref "PORTB") (pin "2") (pinfunction "2_2") (pintype "passive"))
      (node (ref "R34") (pin "2") (pinfunction "2_2") (pintype "passive"))
      (node (ref "R46") (pin "1") (pinfunction "1_1") (pintype "passive"))
      (node (ref "RN1") (pin "2") (pinfunction "1_2") (pintype "passive"))
      (node (ref "RN2") (pin "8") (pinfunction "8_8") (pintype "passive"))
    )
    (net (code "75") (name "Net-(RN1B-2)") (class "Default")
      (node (ref "R34") (pin "1") (pinfunction "1_1") (pintype "passive"))
      (node (ref "RN1") (pin "15") (pinfunction "2_15") (pintype "passive"))
      (node (ref "U2") (pin "12") (pinfunction "G_12") (pintype "input"))
    )
    (net (code "76") (name "Net-(RN1C-1)") (class "Default")
      (node (ref "JP2") (pin "3") (pinfunction "3_3") (pintype "passive"))
      (node (ref "PORTB") (pin "3") (pinfunction "3_3") (pintype "passive"))
      (node (ref "R33") (pin "2") (pinfunction "2_2") (pintype "passive"))
      (node (ref "R47") (pin "1") (pinfunction "1_1") (pintype "passive"))
      (node (ref "RN1") (pin "3") (pinfunction "1_3") (pintype "passive"))
      (node (ref "RN2") (pin "7") (pinfunction "7_7") (pintype "passive"))
    )
    (net (code "77") (name "Net-(RN1C-2)") (class "Default")
      (node (ref "R33") (pin "1") (pinfunction "1_1") (pintype "passive"))
      (node (ref "RN1") (pin "14") (pinfunction "2_14") (pintype "passive"))
      (node (ref "U2") (pin "11") (pinfunction "F_11") (pintype "input"))
    )
    (net (code "78") (name "Net-(RN1D-1)") (class "Default")
      (node (ref "JP2") (pin "4") (pinfunction "4_4") (pintype "passive"))
      (node (ref "PORTB") (pin "4") (pinfunction "4_4") (pintype "passive"))
      (node (ref "R32") (pin "2") (pinfunction "2_2") (pintype "passive"))
      (node (ref "R48") (pin "1") (pinfunction "1_1") (pintype "passive"))
      (node (ref "RN1") (pin "4") (pinfunction "1_4") (pintype "passive"))
      (node (ref "RN2") (pin "6") (pinfunction "6_6") (pintype "passive"))
    )
    (net (code "79") (name "Net-(RN1D-2)") (class "Default")
      (node (ref "R32") (pin "1") (pinfunction "1_1") (pintype "passive"))
      (node (ref "RN1") (pin "13") (pinfunction "2_13") (pintype "passive"))
      (node (ref "U2") (pin "10") (pinfunction "E_10") (pintype "input"))
    )
    (net (code "80") (name "Net-(RN1E-1)") (class "Default")
      (node (ref "JP2") (pin "5") (pinfunction "5_5") (pintype "passive"))
      (node (ref "PORTB") (pin "7") (pinfunction "7_7") (pintype "passive"))
      (node (ref "R31") (pin "2") (pinfunction "2_2") (pintype "passive"))
      (node (ref "R49") (pin "1") (pinfunction "1_1") (pintype "passive"))
      (node (ref "RN1") (pin "5") (pinfunction "1_5") (pintype "passive"))
      (node (ref "RN2") (pin "5") (pinfunction "5_5") (pintype "passive"))
    )
    (net (code "81") (name "Net-(RN1E-2)") (class "Default")
      (node (ref "R31") (pin "1") (pinfunction "1_1") (pintype "passive"))
      (node (ref "RN1") (pin "12") (pinfunction "2_12") (pintype "passive"))
      (node (ref "U2") (pin "5") (pinfunction "D_5") (pintype "input"))
    )
    (net (code "82") (name "Net-(RN1F-1)") (class "Default")
      (node (ref "JP2") (pin "6") (pinfunction "6_6") (pintype "passive"))
      (node (ref "PORTB") (pin "8") (pinfunction "8_8") (pintype "passive"))
      (node (ref "R30") (pin "2") (pinfunction "2_2") (pintype "passive"))
      (node (ref "R50") (pin "1") (pinfunction "1_1") (pintype "passive"))
      (node (ref "RN1") (pin "6") (pinfunction "1_6") (pintype "passive"))
      (node (ref "RN2") (pin "4") (pinfunction "4_4") (pintype "passive"))
    )
    (net (code "83") (name "Net-(RN1F-2)") (class "Default")
      (node (ref "R30") (pin "1") (pinfunction "1_1") (pintype "passive"))
      (node (ref "RN1") (pin "11") (pinfunction "2_11") (pintype "passive"))
      (node (ref "U2") (pin "4") (pinfunction "C_4") (pintype "input"))
    )
    (net (code "84") (name "Net-(RN1G-1)") (class "Default")
      (node (ref "JP2") (pin "7") (pinfunction "7_7") (pintype "passive"))
      (node (ref "PORTB") (pin "9") (pinfunction "9_9") (pintype "passive"))
      (node (ref "R29") (pin "2") (pinfunction "2_2") (pintype "passive"))
      (node (ref "R51") (pin "1") (pinfunction "1_1") (pintype "passive"))
      (node (ref "RN1") (pin "7") (pinfunction "1_7") (pintype "passive"))
      (node (ref "RN2") (pin "3") (pinfunction "3_3") (pintype "passive"))
    )
    (net (code "85") (name "Net-(RN1G-2)") (class "Default")
      (node (ref "R29") (pin "1") (pinfunction "1_1") (pintype "passive"))
      (node (ref "RN1") (pin "10") (pinfunction "2_10") (pintype "passive"))
      (node (ref "U2") (pin "3") (pinfunction "B_3") (pintype "input"))
    )
    (net (code "86") (name "Net-(RN1H-1)") (class "Default")
      (node (ref "JP2") (pin "8") (pinfunction "8_8") (pintype "passive"))
      (node (ref "PORTB") (pin "10") (pinfunction "10_10") (pintype "passive"))
      (node (ref "R28") (pin "2") (pinfunction "2_2") (pintype "passive"))
      (node (ref "R52") (pin "1") (pinfunction "1_1") (pintype "passive"))
      (node (ref "RN1") (pin "8") (pinfunction "1_8") (pintype "passive"))
      (node (ref "RN2") (pin "2") (pinfunction "2_2") (pintype "passive"))
    )
    (net (code "87") (name "Net-(RN1H-2)") (class "Default")
      (node (ref "R28") (pin "1") (pinfunction "1_1") (pintype "passive"))
      (node (ref "RN1") (pin "9") (pinfunction "2_9") (pintype "passive"))
      (node (ref "U2") (pin "2") (pinfunction "A_2") (pintype "input"))
    )
    (net (code "88") (name "Net-(RN3A-2)") (class "Default")
      (node (ref "R44") (pin "1") (pinfunction "1_1") (pintype "passive"))
      (node (ref "RN3") (pin "16") (pinfunction "2_16") (pintype "passive"))
      (node (ref "U1") (pin "14") (pinfunction "H_14") (pintype "input"))
    )
    (net (code "89") (name "Net-(RN3B-1)") (class "Default")
      (node (ref "JP3") (pin "2") (pinfunction "2_2") (pintype "passive"))
      (node (ref "PORTA") (pin "2") (pinfunction "2_2") (pintype "passive"))
      (node (ref "R43") (pin "2") (pinfunction "2_2") (pintype "passive"))
      (node (ref "R54") (pin "2") (pinfunction "2_2") (pintype "passive"))
      (node (ref "RN3") (pin "2") (pinfunction "1_2") (pintype "passive"))
      (node (ref "RN4") (pin "8") (pinfunction "8_8") (pintype "passive"))
    )
    (net (code "90") (name "Net-(RN3B-2)") (class "Default")
      (node (ref "R43") (pin "1") (pinfunction "1_1") (pintype "passive"))
      (node (ref "RN3") (pin "15") (pinfunction "2_15") (pintype "passive"))
      (node (ref "U1") (pin "12") (pinfunction "G_12") (pintype "input"))
    )
    (net (code "91") (name "Net-(RN3C-1)") (class "Default")
      (node (ref "JP3") (pin "3") (pinfunction "3_3") (pintype "passive"))
      (node (ref "PORTA") (pin "3") (pinfunction "3_3") (pintype "passive"))
      (node (ref "R42") (pin "2") (pinfunction "2_2") (pintype "passive"))
      (node (ref "R55") (pin "2") (pinfunction "2_2") (pintype "passive"))
      (node (ref "RN3") (pin "3") (pinfunction "1_3") (pintype "passive"))
      (node (ref "RN4") (pin "7") (pinfunction "7_7") (pintype "passive"))
    )
    (net (code "92") (name "Net-(RN3C-2)") (class "Default")
      (node (ref "R42") (pin "1") (pinfunction "1_1") (pintype "passive"))
      (node (ref "RN3") (pin "14") (pinfunction "2_14") (pintype "passive"))
      (node (ref "U1") (pin "11") (pinfunction "F_11") (pintype "input"))
    )
    (net (code "93") (name "Net-(RN3D-1)") (class "Default")
      (node (ref "JP3") (pin "4") (pinfunction "4_4") (pintype "passive"))
      (node (ref "PORTA") (pin "4") (pinfunction "4_4") (pintype "passive"))
      (node (ref "R41") (pin "2") (pinfunction "2_2") (pintype "passive"))
      (node (ref "R56") (pin "2") (pinfunction "2_2") (pintype "passive"))
      (node (ref "RN3") (pin "4") (pinfunction "1_4") (pintype "passive"))
      (node (ref "RN4") (pin "6") (pinfunction "6_6") (pintype "passive"))
    )
    (net (code "94") (name "Net-(RN3D-2)") (class "Default")
      (node (ref "R41") (pin "1") (pinfunction "1_1") (pintype "passive"))
      (node (ref "RN3") (pin "13") (pinfunction "2_13") (pintype "passive"))
      (node (ref "U1") (pin "10") (pinfunction "E_10") (pintype "input"))
    )
    (net (code "95") (name "Net-(RN3E-1)") (class "Default")
      (node (ref "JP3") (pin "5") (pinfunction "5_5") (pintype "passive"))
      (node (ref "PORTA") (pin "7") (pinfunction "7_7") (pintype "passive"))
      (node (ref "R39") (pin "2") (pinfunction "2_2") (pintype "passive"))
      (node (ref "R57") (pin "2") (pinfunction "2_2") (pintype "passive"))
      (node (ref "RN3") (pin "5") (pinfunction "1_5") (pintype "passive"))
      (node (ref "RN4") (pin "5") (pinfunction "5_5") (pintype "passive"))
    )
    (net (code "96") (name "Net-(RN3E-2)") (class "Default")
      (node (ref "R39") (pin "1") (pinfunction "1_1") (pintype "passive"))
      (node (ref "RN3") (pin "12") (pinfunction "2_12") (pintype "passive"))
      (node (ref "U1") (pin "5") (pinfunction "D_5") (pintype "input"))
    )
    (net (code "97") (name "Net-(RN3F-1)") (class "Default")
      (node (ref "JP3") (pin "6") (pinfunction "6_6") (pintype "passive"))
      (node (ref "PORTA") (pin "8") (pinfunction "8_8") (pintype "passive"))
      (node (ref "R38") (pin "2") (pinfunction "2_2") (pintype "passive"))
      (node (ref "R58") (pin "2") (pinfunction "2_2") (pintype "passive"))
      (node (ref "RN3") (pin "6") (pinfunction "1_6") (pintype "passive"))
      (node (ref "RN4") (pin "4") (pinfunction "4_4") (pintype "passive"))
    )
    (net (code "98") (name "Net-(RN3F-2)") (class "Default")
      (node (ref "R38") (pin "1") (pinfunction "1_1") (pintype "passive"))
      (node (ref "RN3") (pin "11") (pinfunction "2_11") (pintype "passive"))
      (node (ref "U1") (pin "4") (pinfunction "C_4") (pintype "input"))
    )
    (net (code "99") (name "Net-(RN3G-1)") (class "Default")
      (node (ref "JP3") (pin "7") (pinfunction "7_7") (pintype "passive"))
      (node (ref "PORTA") (pin "9") (pinfunction "9_9") (pintype "passive"))
      (node (ref "R37") (pin "2") (pinfunction "2_2") (pintype "passive"))
      (node (ref "R59") (pin "2") (pinfunction "2_2") (pintype "passive"))
      (node (ref "RN3") (pin "7") (pinfunction "1_7") (pintype "passive"))
      (node (ref "RN4") (pin "3") (pinfunction "3_3") (pintype "passive"))
    )
    (net (code "100") (name "Net-(RN3G-2)") (class "Default")
      (node (ref "R37") (pin "1") (pinfunction "1_1") (pintype "passive"))
      (node (ref "RN3") (pin "10") (pinfunction "2_10") (pintype "passive"))
      (node (ref "U1") (pin "3") (pinfunction "B_3") (pintype "input"))
    )
    (net (code "101") (name "Net-(RN3H-1)") (class "Default")
      (node (ref "JP3") (pin "8") (pinfunction "8_8") (pintype "passive"))
      (node (ref "PORTA") (pin "10") (pinfunction "10_10") (pintype "passive"))
      (node (ref "R36") (pin "2") (pinfunction "2_2") (pintype "passive"))
      (node (ref "R60") (pin "2") (pinfunction "2_2") (pintype "passive"))
      (node (ref "RN3") (pin "8") (pinfunction "1_8") (pintype "passive"))
      (node (ref "RN4") (pin "2") (pinfunction "2_2") (pintype "passive"))
    )
    (net (code "102") (name "Net-(RN3H-2)") (class "Default")
      (node (ref "R36") (pin "1") (pinfunction "1_1") (pintype "passive"))
      (node (ref "RN3") (pin "9") (pinfunction "2_9") (pintype "passive"))
      (node (ref "U1") (pin "2") (pinfunction "A_2") (pintype "input"))
    )
    (net (code "103") (name "Net-(SJ1-1)") (class "Default")
      (node (ref "SJ1") (pin "P$1") (pinfunction "1_P$1") (pintype "passive"))
      (node (ref "SJ2") (pin "P$1") (pinfunction "1_P$1") (pintype "passive"))
      (node (ref "SJ3") (pin "1") (pinfunction "1_1") (pintype "passive"))
      (node (ref "U12") (pin "9") (pinfunction "GND_9") (pintype "power_in"))
    )
    (net (code "104") (name "Net-(SJ4-1)") (class "Default")
      (node (ref "SJ4") (pin "P$1") (pinfunction "1_P$1") (pintype "passive"))
      (node (ref "SJ5") (pin "P$1") (pinfunction "1_P$1") (pintype "passive"))
      (node (ref "SJ6") (pin "P$1") (pinfunction "1_P$1") (pintype "passive"))
      (node (ref "U12") (pin "10") (pinfunction "CD+_10") (pintype "passive"))
    )
    (net (code "105") (name "Net-(SJ13-1)") (class "Default")
      (node (ref "SJ13") (pin "P$1") (pinfunction "1_P$1") (pintype "passive"))
      (node (ref "U$1") (pin "PB14") (pinfunction "PB14_PB14") (pintype "bidirectional"))
    )
    (net (code "106") (name "Net-(SJ14-1)") (class "Default")
      (node (ref "SJ14") (pin "P$1") (pinfunction "1_P$1") (pintype "passive"))
      (node (ref "U$1") (pin "VIN2") (pinfunction "VIN2_VIN2") (pintype "power_in"))
    )
    (net (code "107") (name "Net-(SJ16-2)") (class "Default")
      (node (ref "JP9") (pin "2") (pinfunction "2_2") (pintype "passive"))
      (node (ref "SJ15") (pin "2") (pinfunction "2_2") (pintype "passive"))
      (node (ref "SJ16") (pin "P$2") (pinfunction "2_P$2") (pintype "passive"))
    )
    (net (code "108") (name "Net-(SJ18-2)") (class "Default")
      (node (ref "SJ18") (pin "P$2") (pinfunction "2_P$2") (pintype "passive"))
      (node (ref "U7") (pin "5") (pinfunction "VREF_5") (pintype "output"))
      (node (ref "U7B") (pin "5") (pinfunction "VREF_5") (pintype "bidirectional"))
    )
    (net (code "109") (name "Net-(U3A-O)") (class "Default")
      (node (ref "JP5") (pin "1") (pinfunction "1_1") (pintype "passive"))
      (node (ref "PORTC") (pin "1") (pinfunction "1_1") (pintype "passive"))
      (node (ref "U3") (pin "7") (pinfunction "O_7") (pintype "output"))
      (node (ref "U9") (pin "7") (pinfunction "OUT_7") (pintype "output"))
    )
    (net (code "110") (name "Net-(U3B-O)") (class "Default")
      (node (ref "JP5") (pin "2") (pinfunction "2_2") (pintype "passive"))
      (node (ref "PORTC") (pin "2") (pinfunction "2_2") (pintype "passive"))
      (node (ref "U3") (pin "5") (pinfunction "O_5") (pintype "output"))
      (node (ref "U9") (pin "8") (pinfunction "OUT_8") (pintype "output"))
    )
    (net (code "111") (name "Net-(U4A-O)") (class "Default")
      (node (ref "JP5") (pin "4") (pinfunction "4_4") (pintype "passive"))
      (node (ref "PORTC") (pin "4") (pinfunction "4_4") (pintype "passive"))
      (node (ref "U4") (pin "7") (pinfunction "O_7") (pintype "output"))
      (node (ref "U9") (pin "14") (pinfunction "OUT_14") (pintype "output"))
    )
    (net (code "112") (name "Net-(U4B-O)") (class "Default")
      (node (ref "JP5") (pin "3") (pinfunction "3_3") (pintype "passive"))
      (node (ref "PORTC") (pin "3") (pinfunction "3_3") (pintype "passive"))
      (node (ref "U4") (pin "5") (pinfunction "O_5") (pintype "output"))
      (node (ref "U9") (pin "1") (pinfunction "OUT_1") (pintype "output"))
    )
    (net (code "113") (name "Net-(U7-RS)") (class "Default")
      (node (ref "R61") (pin "1") (pinfunction "1_1") (pintype "passive"))
      (node (ref "U7") (pin "8") (pinfunction "RS_8") (pintype "input"))
      (node (ref "U7B") (pin "8") (pinfunction "RS_8") (pintype "bidirectional"))
    )
    (net (code "114") (name "Net-(U8-VOUT)") (class "Default")
      (node (ref "D1") (pin "C") (pinfunction "C_C") (pintype "passive"))
      (node (ref "L1") (pin "2") (pinfunction "2_2") (pintype "passive"))
      (node (ref "U8") (pin "2") (pinfunction "VOUT_2") (pintype "bidirectional"))
      (node (ref "U8B") (pin "7") (pinfunction "OUT_7") (pintype "passive"))
    )
    (net (code "115") (name "Net-(U10A--IN)") (class "Default")
      (node (ref "R1") (pin "1") (pinfunction "1_1") (pintype "passive"))
      (node (ref "R2") (pin "2") (pinfunction "2_2") (pintype "passive"))
      (node (ref "U10") (pin "13") (pinfunction "-IN_13") (pintype "input"))
      (node (ref "U10") (pin "2") (pinfunction "-IN_2") (pintype "input"))
      (node (ref "U10") (pin "6") (pinfunction "-IN_6") (pintype "input"))
      (node (ref "U10") (pin "9") (pinfunction "-IN_9") (pintype "input"))
      (node (ref "U9") (pin "13") (pinfunction "-IN_13") (pintype "input"))
      (node (ref "U9") (pin "2") (pinfunction "-IN_2") (pintype "input"))
      (node (ref "U9") (pin "6") (pinfunction "-IN_6") (pintype "input"))
      (node (ref "U9") (pin "9") (pinfunction "-IN_9") (pintype "input"))
    )
    (net (code "116") (name "Net-(U10A-OUT)") (class "Default")
      (node (ref "JP5") (pin "7") (pinfunction "7_7") (pintype "passive"))
      (node (ref "PORTC") (pin "9") (pinfunction "9_9") (pintype "passive"))
      (node (ref "U10") (pin "1") (pinfunction "OUT_1") (pintype "output"))
      (node (ref "U6") (pin "5") (pinfunction "O_5") (pintype "output"))
    )
    (net (code "117") (name "Net-(U10B-OUT)") (class "Default")
      (node (ref "JP5") (pin "5") (pinfunction "5_5") (pintype "passive"))
      (node (ref "PORTC") (pin "7") (pinfunction "7_7") (pintype "passive"))
      (node (ref "U10") (pin "7") (pinfunction "OUT_7") (pintype "output"))
      (node (ref "U5") (pin "7") (pinfunction "O_7") (pintype "output"))
    )
    (net (code "118") (name "Net-(U10C-OUT)") (class "Default")
      (node (ref "JP5") (pin "6") (pinfunction "6_6") (pintype "passive"))
      (node (ref "PORTC") (pin "8") (pinfunction "8_8") (pintype "passive"))
      (node (ref "U10") (pin "8") (pinfunction "OUT_8") (pintype "output"))
      (node (ref "U5") (pin "5") (pinfunction "O_5") (pintype "output"))
    )
    (net (code "119") (name "Net-(U10D-OUT)") (class "Default")
      (node (ref "JP5") (pin "8") (pinfunction "8_8") (pintype "passive"))
      (node (ref "PORTC") (pin "10") (pinfunction "10_10") (pintype "passive"))
      (node (ref "U10") (pin "14") (pinfunction "OUT_14") (pintype "output"))
      (node (ref "U6") (pin "7") (pinfunction "O_7") (pintype "output"))
    )
    (net (code "120") (name "Net-(U11A-QA)") (class "Default")
      (node (ref "R3") (pin "1") (pinfunction "1_1") (pintype "passive"))
      (node (ref "U11") (pin "15") (pinfunction "QA_15") (pintype "tri_state"))
      (node (ref "U12") (pin "1") (pinfunction "I1_1") (pintype "input"))
    )
    (net (code "121") (name "Net-(U11A-QB)") (class "Default")
      (node (ref "R4") (pin "1") (pinfunction "1_1") (pintype "passive"))
      (node (ref "U11") (pin "1") (pinfunction "QB_1") (pintype "tri_state"))
      (node (ref "U12") (pin "2") (pinfunction "I2_2") (pintype "input"))
    )
    (net (code "122") (name "Net-(U11A-QC)") (class "Default")
      (node (ref "R5") (pin "1") (pinfunction "1_1") (pintype "passive"))
      (node (ref "U11") (pin "2") (pinfunction "QC_2") (pintype "tri_state"))
      (node (ref "U12") (pin "3") (pinfunction "I3_3") (pintype "input"))
    )
    (net (code "123") (name "Net-(U11A-QD)") (class "Default")
      (node (ref "R6") (pin "1") (pinfunction "1_1") (pintype "passive"))
      (node (ref "U11") (pin "3") (pinfunction "QD_3") (pintype "tri_state"))
      (node (ref "U12") (pin "4") (pinfunction "I4_4") (pintype "input"))
    )
    (net (code "124") (name "Net-(U11A-QE)") (class "Default")
      (node (ref "R7") (pin "1") (pinfunction "1_1") (pintype "passive"))
      (node (ref "U11") (pin "4") (pinfunction "QE_4") (pintype "tri_state"))
      (node (ref "U12") (pin "5") (pinfunction "I5_5") (pintype "input"))
    )
    (net (code "125") (name "Net-(U11A-QF)") (class "Default")
      (node (ref "R8") (pin "1") (pinfunction "1_1") (pintype "passive"))
      (node (ref "U11") (pin "5") (pinfunction "QF_5") (pintype "tri_state"))
      (node (ref "U12") (pin "6") (pinfunction "I6_6") (pintype "input"))
    )
    (net (code "126") (name "Net-(U11A-QG)") (class "Default")
      (node (ref "R9") (pin "1") (pinfunction "1_1") (pintype "passive"))
      (node (ref "U11") (pin "6") (pinfunction "QG_6") (pintype "tri_state"))
      (node (ref "U12") (pin "7") (pinfunction "I7_7") (pintype "input"))
    )
    (net (code "127") (name "Net-(U11A-QH)") (class "Default")
      (node (ref "R10") (pin "1") (pinfunction "1_1") (pintype "passive"))
      (node (ref "U11") (pin "7") (pinfunction "QH_7") (pintype "tri_state"))
      (node (ref "U12") (pin "8") (pinfunction "I8_8") (pintype "input"))
    )
    (net (code "128") (name "OLAT") (class "Default")
      (node (ref "IC3") (pin "12") (pinfunction "RCK_12") (pintype "input"))
      (node (ref "R21") (pin "1") (pinfunction "1_1") (pintype "passive"))
      (node (ref "U$1") (pin "PA8") (pinfunction "PA8_PA8") (pintype "bidirectional"))
      (node (ref "U11") (pin "12") (pinfunction "RCK_12") (pintype "input"))
    )
    (net (code "129") (name "SCK") (class "Default")
      (node (ref "IC3") (pin "11") (pinfunction "SCK_11") (pintype "input"))
      (node (ref "JP9") (pin "3") (pinfunction "3_3") (pintype "passive"))
      (node (ref "R19") (pin "1") (pinfunction "1_1") (pintype "passive"))
      (node (ref "U$1") (pin "PB3") (pinfunction "PB3_PB3") (pintype "bidirectional"))
      (node (ref "U11") (pin "11") (pinfunction "SCK_11") (pintype "input"))
    )
    (net (code "130") (name "SCK2") (class "Default")
      (node (ref "U$1") (pin "PB10") (pinfunction "PB10_PB10") (pintype "bidirectional"))
      (node (ref "U1") (pin "7") (pinfunction "CLK_7") (pintype "input"))
      (node (ref "U2") (pin "7") (pinfunction "CLK_7") (pintype "input"))
    )
    (net (code "131") (name "SLNK1") (class "Default")
      (node (ref "IC3") (pin "14") (pinfunction "SER_14") (pintype "input"))
      (node (ref "SJ17") (pin "P$1") (pinfunction "1_P$1") (pintype "passive"))
      (node (ref "U11") (pin "9") (pinfunction "QH*_9") (pintype "tri_state"))
    )
    (net (code "132") (name "SLNK2") (class "Default")
      (node (ref "IC3") (pin "9") (pinfunction "QH*_9") (pintype "tri_state"))
      (node (ref "SJ16") (pin "P$1") (pinfunction "1_P$1") (pintype "passive"))
    )
    (net (code "133") (name "SLNK3") (class "Default")
      (node (ref "U1") (pin "13") (pinfunction "QH_13") (pintype "output"))
      (node (ref "U2") (pin "1") (pinfunction "SER_1") (pintype "input"))
    )
    (net (code "134") (name "SRV1") (class "Default")
      (node (ref "JP7") (pin "2") (pinfunction "2_2") (pintype "passive"))
      (node (ref "R25") (pin "2") (pinfunction "2_2") (pintype "passive"))
      (node (ref "U$1") (pin "PC9") (pinfunction "PC9_PC9") (pintype "bidirectional"))
    )
    (net (code "135") (name "SRV2") (class "Default")
      (node (ref "JP7") (pin "1") (pinfunction "1_1") (pintype "passive"))
      (node (ref "R24") (pin "2") (pinfunction "2_2") (pintype "passive"))
      (node (ref "U$1") (pin "PC7") (pinfunction "PC7_PC7") (pintype "bidirectional"))
    )
    (net (code "136") (name "SRV3") (class "Default")
      (node (ref "JP11") (pin "2") (pinfunction "2_2") (pintype "passive"))
      (node (ref "R26") (pin "2") (pinfunction "2_2") (pintype "passive"))
      (node (ref "U$1") (pin "PC8") (pinfunction "PC8_PC8") (pintype "bidirectional"))
    )
    (net (code "137") (name "SRV4") (class "Default")
      (node (ref "JP11") (pin "1") (pinfunction "1_1") (pintype "passive"))
      (node (ref "R27") (pin "2") (pinfunction "2_2") (pintype "passive"))
      (node (ref "U$1") (pin "PC6") (pinfunction "PC6_PC6") (pintype "bidirectional"))
    )
    (net (code "138") (name "SRV5") (class "Default")
      (node (ref "JP12") (pin "2") (pinfunction "2_2") (pintype "passive"))
      (node (ref "R64") (pin "2") (pinfunction "2_2") (pintype "passive"))
      (node (ref "U$1") (pin "PF1-PH1") (pinfunction "PF1-PH1_PF1-PH1") (pintype "bidirectional"))
    )
    (net (code "139") (name "SRV6") (class "Default")
      (node (ref "JP12") (pin "1") (pinfunction "1_1") (pintype "passive"))
      (node (ref "R65") (pin "2") (pinfunction "2_2") (pintype "passive"))
      (node (ref "U$1") (pin "PA15") (pinfunction "PA15_PA15") (pintype "bidirectional"))
    )
    (net (code "140") (name "SRV7") (class "Default")
      (node (ref "JP16") (pin "2") (pinfunction "2_2") (pintype "passive"))
      (node (ref "R66") (pin "2") (pinfunction "2_2") (pintype "passive"))
      (node (ref "U$1") (pin "PC12") (pinfunction "PC12_PC12") (pintype "bidirectional"))
    )
    (net (code "141") (name "SRV8") (class "Default")
      (node (ref "JP16") (pin "1") (pinfunction "1_1") (pintype "passive"))
      (node (ref "R67") (pin "2") (pinfunction "2_2") (pintype "passive"))
      (node (ref "U$1") (pin "PD2") (pinfunction "PD2_PD2") (pintype "bidirectional"))
    )
    (net (code "142") (name "TIN1") (class "Default")
      (node (ref "U$1") (pin "PC0") (pinfunction "PC0_PC0") (pintype "bidirectional"))
      (node (ref "U3") (pin "2") (pinfunction "I_2") (pintype "input"))
      (node (ref "U9") (pin "5") (pinfunction "+IN_5") (pintype "input"))
    )
    (net (code "143") (name "TIN2") (class "Default")
      (node (ref "U$1") (pin "PC3") (pinfunction "PC3_PC3") (pintype "bidirectional"))
      (node (ref "U3") (pin "4") (pinfunction "I_4") (pintype "input"))
      (node (ref "U9") (pin "10") (pinfunction "+IN_10") (pintype "input"))
    )
    (net (code "144") (name "TIN3") (class "Default")
      (node (ref "U$1") (pin "PA4") (pinfunction "PA4_PA4") (pintype "bidirectional"))
      (node (ref "U4") (pin "4") (pinfunction "I_4") (pintype "input"))
      (node (ref "U9") (pin "3") (pinfunction "+IN_3") (pintype "input"))
    )
    (net (code "145") (name "TIN4") (class "Default")
      (node (ref "U$1") (pin "PA0") (pinfunction "PA0_PA0") (pintype "bidirectional"))
      (node (ref "U4") (pin "2") (pinfunction "I_2") (pintype "input"))
      (node (ref "U9") (pin "12") (pinfunction "+IN_12") (pintype "input"))
    )
    (net (code "146") (name "TIN5") (class "Default")
      (node (ref "U$1") (pin "PB1") (pinfunction "PB1_PB1") (pintype "bidirectional"))
      (node (ref "U10") (pin "5") (pinfunction "+IN_5") (pintype "input"))
      (node (ref "U5") (pin "2") (pinfunction "I_2") (pintype "input"))
    )
    (net (code "147") (name "TIN6") (class "Default")
      (node (ref "U$1") (pin "PB15") (pinfunction "PB15_PB15") (pintype "bidirectional"))
      (node (ref "U10") (pin "10") (pinfunction "+IN_10") (pintype "input"))
      (node (ref "U5") (pin "4") (pinfunction "I_4") (pintype "input"))
    )
    (net (code "148") (name "TIN7") (class "Default")
      (node (ref "U$1") (pin "PB2") (pinfunction "PB2_PB2") (pintype "bidirectional"))
      (node (ref "U10") (pin "3") (pinfunction "+IN_3") (pintype "input"))
      (node (ref "U6") (pin "4") (pinfunction "I_4") (pintype "input"))
    )
    (net (code "149") (name "TIN8") (class "Default")
      (node (ref "U$1") (pin "PB12") (pinfunction "PB12_PB12") (pintype "bidirectional"))
      (node (ref "U10") (pin "12") (pinfunction "+IN_12") (pintype "input"))
      (node (ref "U6") (pin "2") (pinfunction "I_2") (pintype "input"))
    )
    (net (code "150") (name "V+") (class "Default")
      (node (ref "C1") (pin "1") (pinfunction "1_1") (pintype "passive"))
      (node (ref "C2") (pin "+") (pinfunction "+_+") (pintype "passive"))
      (node (ref "L1") (pin "1") (pinfunction "1_1") (pintype "passive"))
      (node (ref "U$1") (pin "E5V") (pinfunction "E5V_E5V") (pintype "power_in"))
      (node (ref "U8") (pin "3") (pinfunction "FB_3") (pintype "bidirectional"))
      (node (ref "U8B") (pin "1") (pinfunction "FB_1") (pintype "input"))
    )
    (net (code "151") (name "unconnected-(H1-MOUNT-PadB3,3)") (class "Default")
      (node (ref "H1") (pin "B3,3") (pinfunction "MOUNT_B3,3") (pintype "passive"))
    )
    (net (code "152") (name "unconnected-(H2-MOUNT-PadB3,3)") (class "Default")
      (node (ref "H2") (pin "B3,3") (pinfunction "MOUNT_B3,3") (pintype "passive"))
    )
    (net (code "153") (name "unconnected-(H3-MOUNT-PadB3,3)") (class "Default")
      (node (ref "H3") (pin "B3,3") (pinfunction "MOUNT_B3,3") (pintype "passive"))
    )
    (net (code "154") (name "unconnected-(H4-MOUNT-PadB3,3)") (class "Default")
      (node (ref "H4") (pin "B3,3") (pinfunction "MOUNT_B3,3") (pintype "passive"))
    )
    (net (code "155") (name "unconnected-(U$1-PadBOOT0)") (class "Default")
      (node (ref "U$1") (pin "BOOT0") (pinfunction "BOOT0_BOOT0") (pintype "bidirectional"))
    )
    (net (code "156") (name "unconnected-(U$1-PadIOREF2)") (class "Default")
      (node (ref "U$1") (pin "IOREF2") (pinfunction "IOREF2_IOREF2") (pintype "input"))
    )
    (net (code "157") (name "unconnected-(U$1-PadNC1-PF7)") (class "Default")
      (node (ref "U$1") (pin "NC1-PF7") (pinfunction "NC1-PF7_NC1-PF7") (pintype "bidirectional"))
    )
    (net (code "158") (name "unconnected-(U$1-PadNC2-PF6)") (class "Default")
      (node (ref "U$1") (pin "NC2-PF6") (pinfunction "NC2-PF6_NC2-PF6") (pintype "bidirectional"))
    )
    (net (code "159") (name "unconnected-(U$1-PadNC3)") (class "Default")
      (node (ref "U$1") (pin "NC3") (pinfunction "NC3_NC3") (pintype "no_connect"))
    )
    (net (code "160") (name "unconnected-(U$1-PadNC4)") (class "Default")
      (node (ref "U$1") (pin "NC4") (pinfunction "NC4_NC4") (pintype "no_connect"))
    )
    (net (code "161") (name "unconnected-(U$1-PadNC5-PD8)") (class "Default")
      (node (ref "U$1") (pin "NC5-PD8") (pinfunction "NC5-PD8_NC5-PD8") (pintype "bidirectional"))
    )
    (net (code "162") (name "unconnected-(U$1-PadNC6-PB11)") (class "Default")
      (node (ref "U$1") (pin "NC6-PB11") (pinfunction "NC6-PB11_NC6-PB11") (pintype "no_connect"))
    )
    (net (code "163") (name "unconnected-(U$1-PadNC7-PF5)") (class "Default")
      (node (ref "U$1") (pin "NC7-PF5") (pinfunction "NC7-PF5_NC7-PF5") (pintype "bidirectional"))
    )
    (net (code "164") (name "unconnected-(U$1-PadNC8-PF4)") (class "Default")
      (node (ref "U$1") (pin "NC8-PF4") (pinfunction "NC8-PF4_NC8-PF4") (pintype "bidirectional"))
    )
    (net (code "165") (name "unconnected-(U$1-PadNRESET)") (class "Default")
      (node (ref "U$1") (pin "NRESET") (pinfunction "NRESET_NRESET") (pintype "input"))
    )
    (net (code "166") (name "unconnected-(U$1-PadPA1)") (class "Default")
      (node (ref "U$1") (pin "PA1") (pinfunction "PA1_PA1") (pintype "bidirectional"))
    )
    (net (code "167") (name "unconnected-(U$1-PadPA2)") (class "Default")
      (node (ref "U$1") (pin "PA2") (pinfunction "PA2_PA2") (pintype "bidirectional"))
    )
    (net (code "168") (name "unconnected-(U$1-PadPA3)") (class "Default")
      (node (ref "U$1") (pin "PA3") (pinfunction "PA3_PA3") (pintype "bidirectional"))
    )
    (net (code "169") (name "unconnected-(U$1-PadPA5)") (class "Default")
      (node (ref "U$1") (pin "PA5") (pinfunction "PA5_PA5") (pintype "bidirectional"))
    )
    (net (code "170") (name "unconnected-(U$1-PadPA7)") (class "Default")
      (node (ref "U$1") (pin "PA7") (pinfunction "PA7_PA7") (pintype "bidirectional"))
    )
    (net (code "171") (name "unconnected-(U$1-PadPA9)") (class "Default")
      (node (ref "U$1") (pin "PA9") (pinfunction "PA9_PA9") (pintype "bidirectional"))
    )
    (net (code "172") (name "unconnected-(U$1-PadPA10)") (class "Default")
      (node (ref "U$1") (pin "PA10") (pinfunction "PA10_PA10") (pintype "bidirectional"))
    )
    (net (code "173") (name "unconnected-(U$1-PadPA11)") (class "Default")
      (node (ref "U$1") (pin "PA11") (pinfunction "PA11_PA11") (pintype "bidirectional"))
    )
    (net (code "174") (name "unconnected-(U$1-PadPA12)") (class "Default")
      (node (ref "U$1") (pin "PA12") (pinfunction "PA12_PA12") (pintype "bidirectional"))
    )
    (net (code "175") (name "unconnected-(U$1-PadPA13)") (class "Default")
      (node (ref "U$1") (pin "PA13") (pinfunction "PA13_PA13") (pintype "bidirectional"))
    )
    (net (code "176") (name "unconnected-(U$1-PadPA14)") (class "Default")
      (node (ref "U$1") (pin "PA14") (pinfunction "PA14_PA14") (pintype "bidirectional"))
    )
    (net (code "177") (name "unconnected-(U$1-PadPB0)") (class "Default")
      (node (ref "U$1") (pin "PB0") (pinfunction "PB0_PB0") (pintype "bidirectional"))
    )
    (net (code "178") (name "unconnected-(U$1-PadPB13)") (class "Default")
      (node (ref "U$1") (pin "PB13") (pinfunction "PB13_PB13") (pintype "bidirectional"))
    )
    (net (code "179") (name "unconnected-(U$1-PadPC1)") (class "Default")
      (node (ref "U$1") (pin "PC1") (pinfunction "PC1_PC1") (pintype "bidirectional"))
    )
    (net (code "180") (name "unconnected-(U$1-PadPC4)") (class "Default")
      (node (ref "U$1") (pin "PC4") (pinfunction "PC4_PC4") (pintype "bidirectional"))
    )
    (net (code "181") (name "unconnected-(U$1-PadPC5)") (class "Default")
      (node (ref "U$1") (pin "PC5") (pinfunction "PC5_PC5") (pintype "bidirectional"))
    )
    (net (code "182") (name "unconnected-(U$1-PadPC13)") (class "Default")
      (node (ref "U$1") (pin "PC13") (pinfunction "PC13_PC13") (pintype "bidirectional"))
    )
    (net (code "183") (name "unconnected-(U$1-PadPC14)") (class "Default")
      (node (ref "U$1") (pin "PC14") (pinfunction "PC14_PC14") (pintype "bidirectional"))
    )
    (net (code "184") (name "unconnected-(U$1-PadPC15)") (class "Default")
      (node (ref "U$1") (pin "PC15") (pinfunction "PC15_PC15") (pintype "bidirectional"))
    )
    (net (code "185") (name "unconnected-(U$1-PadPF0-PH0)") (class "Default")
      (node (ref "U$1") (pin "PF0-PH0") (pinfunction "PF0-PH0_PF0-PH0") (pintype "bidirectional"))
    )
  )
)
